# A500_GRAKA_26.net
KiCad netlist of a schematic drawn in EAGLE
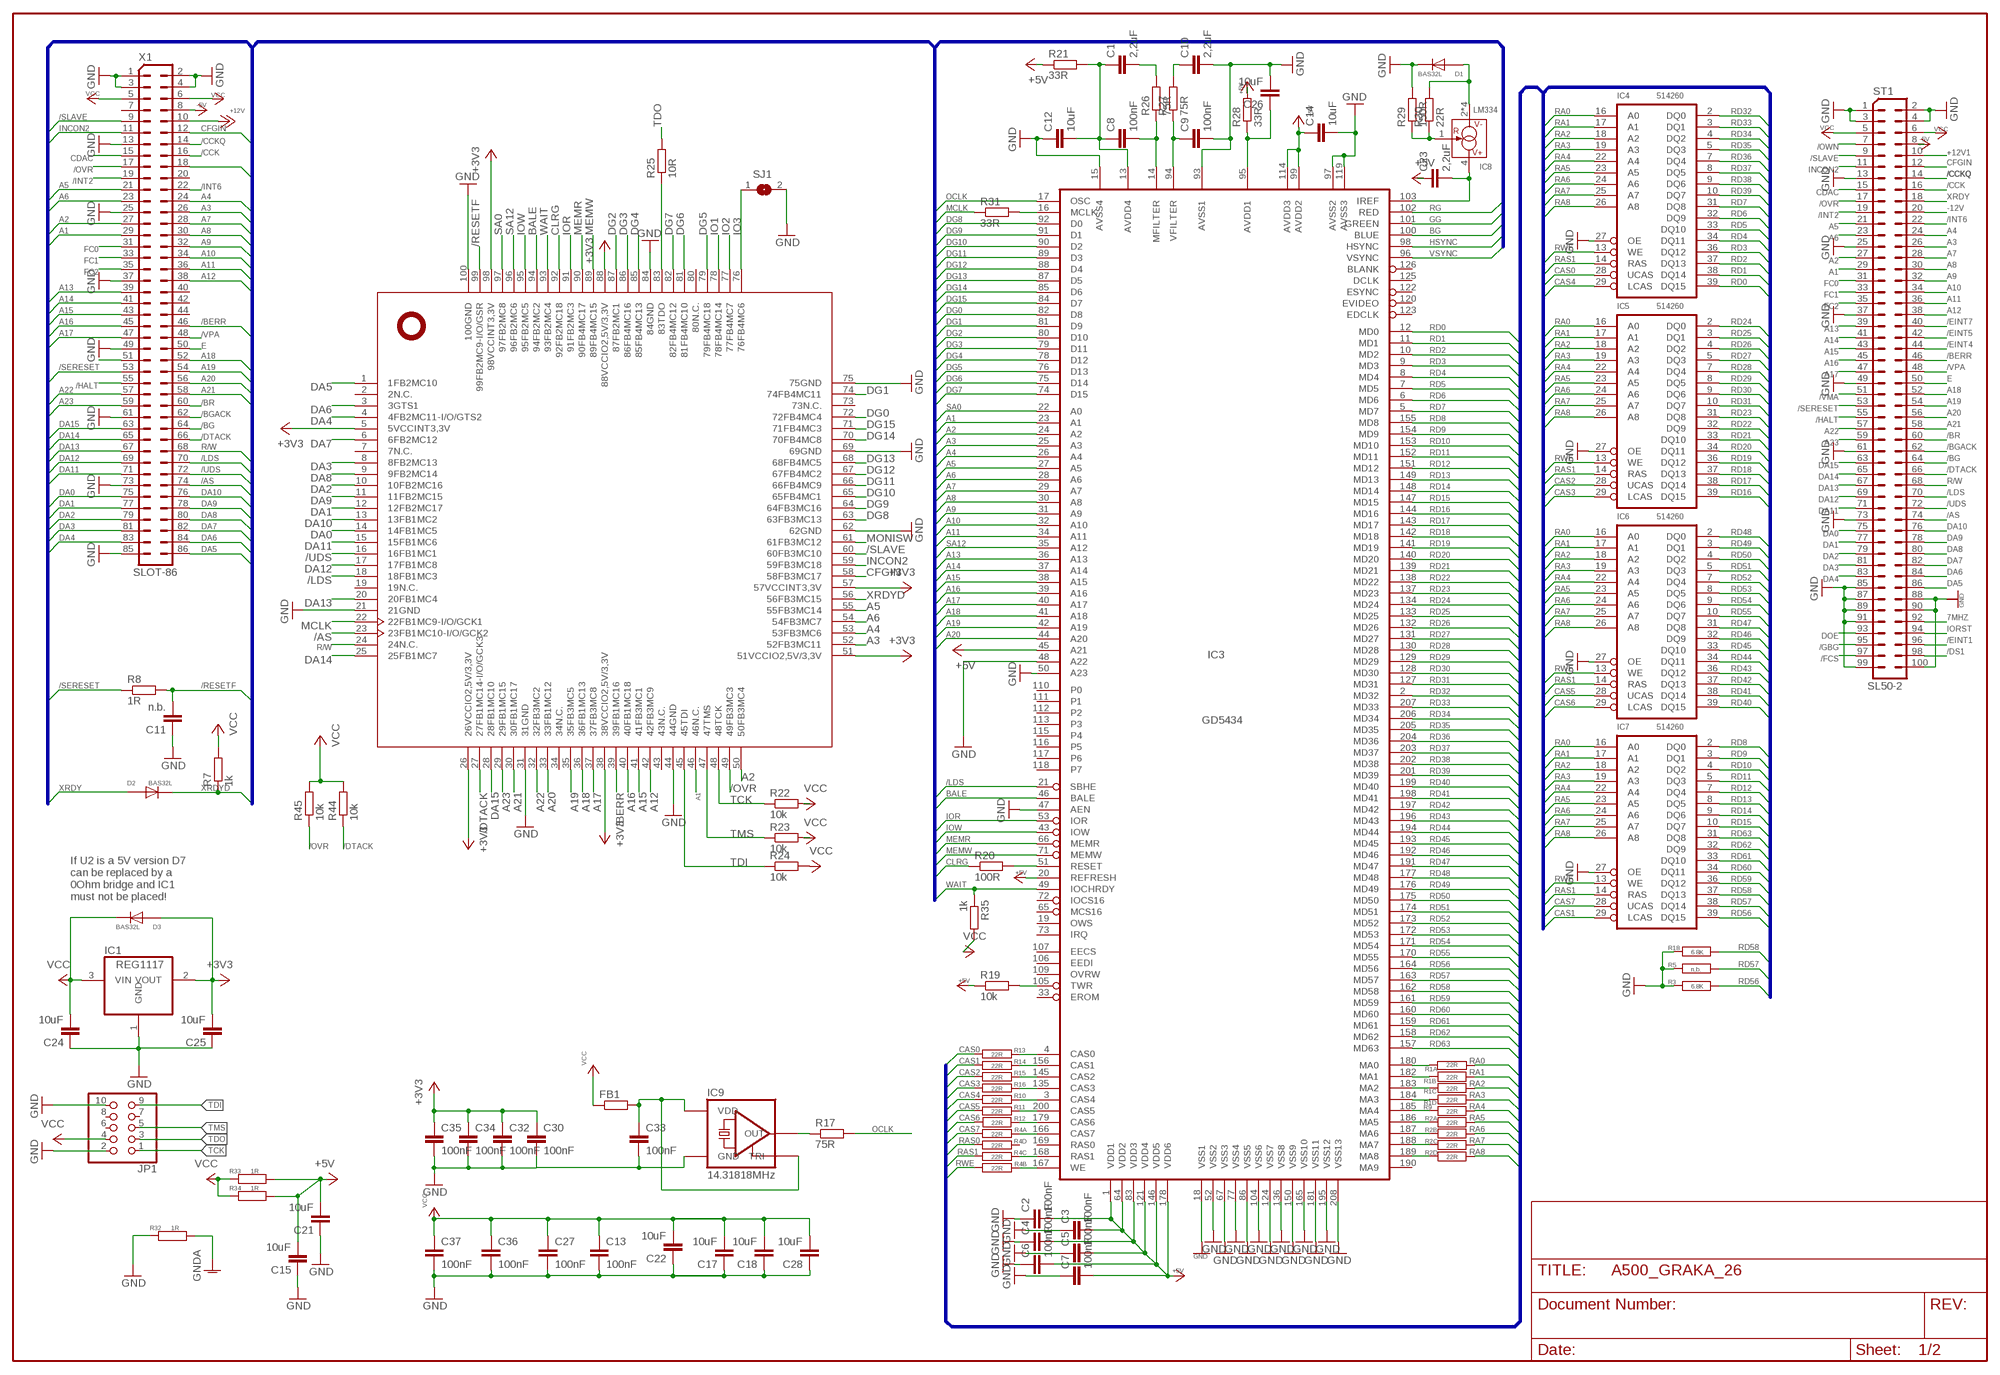
[diagram p0: schematic, sheet 1]
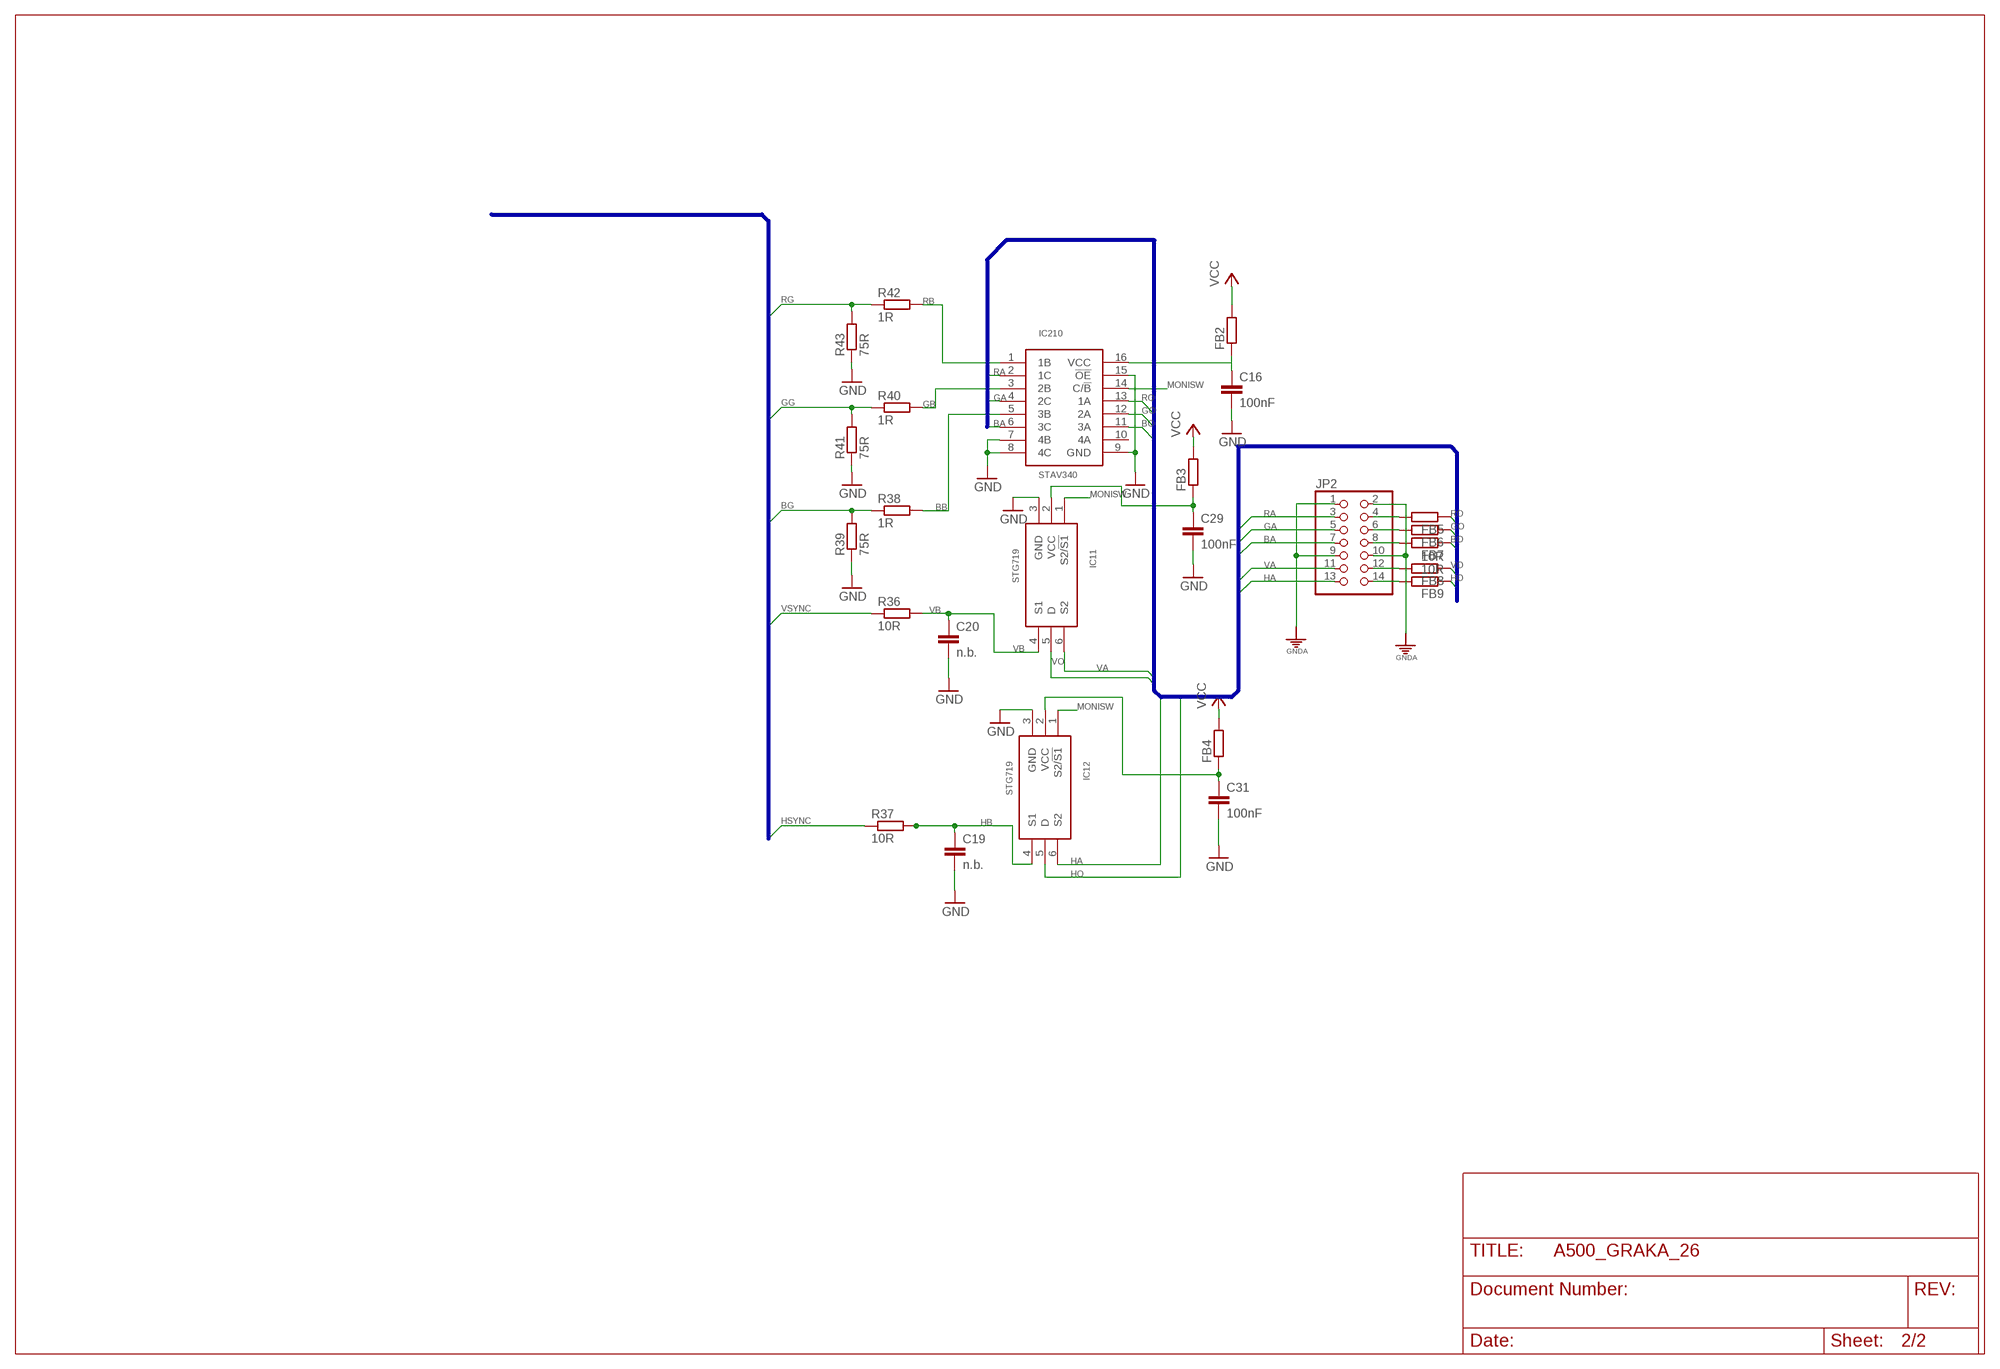
[diagram p1: schematic, sheet 2]

(export (version "E")
  (design (tool "Eeschema 10.0.6"))
  (components
    (comp (ref "C1")
      (value "2,2uF")
      (footprint "eagle-import:C0805K")
      (libsource (lib "eagle-import") (part "C-EUC0805K"))
    )
    (comp (ref "C2")
      (value "100nF")
      (footprint "eagle-import:C0805K")
      (libsource (lib "eagle-import") (part "C-EUC0805K"))
    )
    (comp (ref "C3")
      (value "100nF")
      (footprint "eagle-import:C0805K")
      (libsource (lib "eagle-import") (part "C-EUC0805K"))
    )
    (comp (ref "C4")
      (value "100nF")
      (footprint "eagle-import:C0805K")
      (libsource (lib "eagle-import") (part "C-EUC0805K"))
    )
    (comp (ref "C5")
      (value "100nF")
      (footprint "eagle-import:C0805K")
      (libsource (lib "eagle-import") (part "C-EUC0805K"))
    )
    (comp (ref "C6")
      (value "100nF")
      (footprint "eagle-import:C0805K")
      (libsource (lib "eagle-import") (part "C-EUC0805K"))
    )
    (comp (ref "C7")
      (value "100nF")
      (footprint "eagle-import:C0805K")
      (libsource (lib "eagle-import") (part "C-EUC0805K"))
    )
    (comp (ref "C8")
      (value "100nF")
      (footprint "eagle-import:C0805K")
      (libsource (lib "eagle-import") (part "C-EUC0805K"))
    )
    (comp (ref "C9")
      (value "100nF")
      (footprint "eagle-import:C0805K")
      (libsource (lib "eagle-import") (part "C-EUC0805K"))
    )
    (comp (ref "C10")
      (value "2,2uF")
      (footprint "eagle-import:C0805K")
      (libsource (lib "eagle-import") (part "C-EUC0805K"))
    )
    (comp (ref "C11")
      (value "n.b.")
      (footprint "eagle-import:C0805K")
      (libsource (lib "eagle-import") (part "C-EUC0805K"))
    )
    (comp (ref "C12")
      (value "10uF")
      (footprint "eagle-import:C0805K")
      (libsource (lib "eagle-import") (part "C-EUC0805K"))
    )
    (comp (ref "C13")
      (value "100nF")
      (footprint "eagle-import:C0805K")
      (libsource (lib "eagle-import") (part "C-EUC0805K"))
    )
    (comp (ref "C14")
      (value "10uF")
      (footprint "eagle-import:C0805K")
      (libsource (lib "eagle-import") (part "C-EUC0805K"))
    )
    (comp (ref "C15")
      (value "10uF")
      (footprint "eagle-import:C0805K")
      (libsource (lib "eagle-import") (part "C-EUC0805K"))
    )
    (comp (ref "C17")
      (value "10uF")
      (footprint "eagle-import:C0805K")
      (libsource (lib "eagle-import") (part "C-EUC0805K"))
    )
    (comp (ref "C18")
      (value "10uF")
      (footprint "eagle-import:C0805K")
      (libsource (lib "eagle-import") (part "C-EUC0805K"))
    )
    (comp (ref "C21")
      (value "10uF")
      (footprint "eagle-import:C0805K")
      (libsource (lib "eagle-import") (part "C-EUC0805K"))
    )
    (comp (ref "C22")
      (value "10uF")
      (footprint "eagle-import:C0805K")
      (libsource (lib "eagle-import") (part "C-EUC0805K"))
    )
    (comp (ref "C23")
      (value "2,2uF")
      (footprint "eagle-import:C0805K")
      (libsource (lib "eagle-import") (part "C-EUC0805K"))
    )
    (comp (ref "C24")
      (value "10uF")
      (footprint "eagle-import:C0805K")
      (libsource (lib "eagle-import") (part "C-EUC0805K"))
    )
    (comp (ref "C25")
      (value "10uF")
      (footprint "eagle-import:C0805K")
      (libsource (lib "eagle-import") (part "C-EUC0805K"))
    )
    (comp (ref "C26")
      (value "10uF")
      (footprint "eagle-import:C0805K")
      (libsource (lib "eagle-import") (part "C-EUC0805K"))
    )
    (comp (ref "C27")
      (value "100nF")
      (footprint "eagle-import:C0805K")
      (libsource (lib "eagle-import") (part "C-EUC0805K"))
    )
    (comp (ref "C28")
      (value "10uF")
      (footprint "eagle-import:C0805K")
      (libsource (lib "eagle-import") (part "C-EUC0805K"))
    )
    (comp (ref "C30")
      (value "100nF")
      (footprint "eagle-import:C0805K")
      (libsource (lib "eagle-import") (part "C-EUC0805K"))
    )
    (comp (ref "C32")
      (value "100nF")
      (footprint "eagle-import:C0805K")
      (libsource (lib "eagle-import") (part "C-EUC0805K"))
    )
    (comp (ref "C33")
      (value "100nF")
      (footprint "eagle-import:C0805K")
      (libsource (lib "eagle-import") (part "C-EUC0805K"))
    )
    (comp (ref "C34")
      (value "100nF")
      (footprint "eagle-import:C0805K")
      (libsource (lib "eagle-import") (part "C-EUC0805K"))
    )
    (comp (ref "C35")
      (value "100nF")
      (footprint "eagle-import:C0805K")
      (libsource (lib "eagle-import") (part "C-EUC0805K"))
    )
    (comp (ref "C36")
      (value "100nF")
      (footprint "eagle-import:C0805K")
      (libsource (lib "eagle-import") (part "C-EUC0805K"))
    )
    (comp (ref "C37")
      (value "100nF")
      (footprint "eagle-import:C0805K")
      (libsource (lib "eagle-import") (part "C-EUC0805K"))
    )
    (comp (ref "D1")
      (value "BAS32L")
      (footprint "eagle-import:SOD-80")
      (libsource (lib "eagle-import") (part "D-BAS32L"))
    )
    (comp (ref "D2")
      (value "BAS32L")
      (footprint "eagle-import:SOD-80")
      (libsource (lib "eagle-import") (part "D-BAS32L"))
    )
    (comp (ref "D3")
      (value "BAS32L")
      (footprint "eagle-import:SOD-80")
      (libsource (lib "eagle-import") (part "D-BAS32L"))
    )
    (comp (ref "FB1")
      (value "R-EU_R0805")
      (footprint "eagle-import:R0805")
      (libsource (lib "eagle-import") (part "R-EU_R0805"))
    )
    (comp (ref "IC1")
      (value "REG1117")
      (footprint "eagle-import:SOT223")
      (libsource (lib "eagle-import") (part "REG1117"))
    )
    (comp (ref "IC2")
      (value "XC95144XLTQ100")
      (footprint "eagle-import:TQ100")
      (libsource (lib "eagle-import") (part "XC9572XLTQ100"))
    )
    (comp (ref "IC3")
      (value "GD5434")
      (footprint "eagle-import:PQFP-208@3")
      (libsource (lib "eagle-import") (part "GD5434@3"))
    )
    (comp (ref "IC4")
      (value "514260")
      (footprint "eagle-import:SOJ40_4")
      (libsource (lib "eagle-import") (part "514260"))
    )
    (comp (ref "IC5")
      (value "514260")
      (footprint "eagle-import:SOJ40_4")
      (libsource (lib "eagle-import") (part "514260"))
    )
    (comp (ref "IC6")
      (value "514260")
      (footprint "eagle-import:SOJ40_4")
      (libsource (lib "eagle-import") (part "514260"))
    )
    (comp (ref "IC7")
      (value "514260")
      (footprint "eagle-import:SOJ40_4")
      (libsource (lib "eagle-import") (part "514260"))
    )
    (comp (ref "IC8")
      (value "LM334")
      (footprint "eagle-import:SO08")
      (libsource (lib "eagle-import") (part "LM34M(TI)3"))
    )
    (comp (ref "IC9")
      (value "14.31818MHz")
      (footprint "eagle-import:7X5")
      (libsource (lib "eagle-import") (part "CSX-750FCFC(5V)"))
    )
    (comp (ref "JP1")
      (value "PINHD-2X5_2.54-SMD")
      (footprint "eagle-import:2X05SMD")
      (libsource (lib "eagle-import") (part "PINHD-2X5_2.54-SMD"))
    )
    (comp (ref "R1")
      (value "22R")
      (footprint "eagle-import:R-NETZ")
      (libsource (lib "eagle-import") (part "R-NETZ"))
    )
    (comp (ref "R2")
      (value "22R")
      (footprint "eagle-import:R-NETZ")
      (libsource (lib "eagle-import") (part "R-NETZ"))
    )
    (comp (ref "R3")
      (value "6.8K")
      (footprint "eagle-import:0805@2")
      (libsource (lib "eagle-import") (part "R-MELF@4"))
    )
    (comp (ref "R4")
      (value "22R")
      (footprint "eagle-import:R-NETZ")
      (libsource (lib "eagle-import") (part "R-NETZ"))
    )
    (comp (ref "R5")
      (value "n.b.")
      (footprint "eagle-import:0805@2")
      (libsource (lib "eagle-import") (part "R-MELF@4"))
    )
    (comp (ref "R7")
      (value "1k")
      (footprint "eagle-import:R0805")
      (libsource (lib "eagle-import") (part "R-EU_R0805"))
    )
    (comp (ref "R8")
      (value "1R")
      (footprint "eagle-import:R0805")
      (libsource (lib "eagle-import") (part "R-EU_R0805"))
    )
    (comp (ref "R9")
      (value "22R")
      (footprint "eagle-import:0805@2")
      (libsource (lib "eagle-import") (part "R-MELF@4"))
    )
    (comp (ref "R10")
      (value "22R")
      (footprint "eagle-import:0805@2")
      (libsource (lib "eagle-import") (part "R-MELF@4"))
    )
    (comp (ref "R11")
      (value "22R")
      (footprint "eagle-import:0805@2")
      (libsource (lib "eagle-import") (part "R-MELF@4"))
    )
    (comp (ref "R12")
      (value "22R")
      (footprint "eagle-import:0805@2")
      (libsource (lib "eagle-import") (part "R-MELF@4"))
    )
    (comp (ref "R13")
      (value "22R")
      (footprint "eagle-import:0805@2")
      (libsource (lib "eagle-import") (part "R-MELF@4"))
    )
    (comp (ref "R14")
      (value "22R")
      (footprint "eagle-import:0805@2")
      (libsource (lib "eagle-import") (part "R-MELF@4"))
    )
    (comp (ref "R15")
      (value "22R")
      (footprint "eagle-import:0805@2")
      (libsource (lib "eagle-import") (part "R-MELF@4"))
    )
    (comp (ref "R16")
      (value "22R")
      (footprint "eagle-import:0805@2")
      (libsource (lib "eagle-import") (part "R-MELF@4"))
    )
    (comp (ref "R17")
      (value "75R")
      (footprint "eagle-import:R0805")
      (libsource (lib "eagle-import") (part "R-EU_R0805"))
    )
    (comp (ref "R18")
      (value "6.8K")
      (footprint "eagle-import:0805@2")
      (libsource (lib "eagle-import") (part "R-MELF@4"))
    )
    (comp (ref "R19")
      (value "10k")
      (footprint "eagle-import:R0805")
      (libsource (lib "eagle-import") (part "R-EU_R0805"))
    )
    (comp (ref "R20")
      (value "100R")
      (footprint "eagle-import:R0805")
      (libsource (lib "eagle-import") (part "R-EU_R0805"))
    )
    (comp (ref "R21")
      (value "33R")
      (footprint "eagle-import:R0805")
      (libsource (lib "eagle-import") (part "R-EU_R0805"))
    )
    (comp (ref "R22")
      (value "10k")
      (footprint "eagle-import:R0805")
      (libsource (lib "eagle-import") (part "R-EU_R0805"))
    )
    (comp (ref "R23")
      (value "10k")
      (footprint "eagle-import:R0805")
      (libsource (lib "eagle-import") (part "R-EU_R0805"))
    )
    (comp (ref "R24")
      (value "10k")
      (footprint "eagle-import:R0805")
      (libsource (lib "eagle-import") (part "R-EU_R0805"))
    )
    (comp (ref "R25")
      (value "10R")
      (footprint "eagle-import:R0805")
      (libsource (lib "eagle-import") (part "R-EU_R0805"))
    )
    (comp (ref "R26")
      (value "75R")
      (footprint "eagle-import:R0805")
      (libsource (lib "eagle-import") (part "R-EU_R0805"))
    )
    (comp (ref "R27")
      (value "75R")
      (footprint "eagle-import:R0805")
      (libsource (lib "eagle-import") (part "R-EU_R0805"))
    )
    (comp (ref "R28")
      (value "33R")
      (footprint "eagle-import:R0805")
      (libsource (lib "eagle-import") (part "R-EU_R0805"))
    )
    (comp (ref "R29")
      (value "150R")
      (footprint "eagle-import:R0805")
      (libsource (lib "eagle-import") (part "R-EU_R0805"))
    )
    (comp (ref "R30")
      (value "22R")
      (footprint "eagle-import:R0805")
      (libsource (lib "eagle-import") (part "R-EU_R0805"))
    )
    (comp (ref "R31")
      (value "33R")
      (footprint "eagle-import:R0805")
      (libsource (lib "eagle-import") (part "R-EU_R0805"))
    )
    (comp (ref "R32")
      (value "1R")
      (footprint "eagle-import:0204")
      (libsource (lib "eagle-import") (part "R-MELF@3"))
    )
    (comp (ref "R33")
      (value "1R")
      (footprint "eagle-import:0204")
      (libsource (lib "eagle-import") (part "R-MELF@3"))
    )
    (comp (ref "R34")
      (value "1R")
      (footprint "eagle-import:0204")
      (libsource (lib "eagle-import") (part "R-MELF@3"))
    )
    (comp (ref "R35")
      (value "1k")
      (footprint "eagle-import:R0805")
      (libsource (lib "eagle-import") (part "R-EU_R0805"))
    )
    (comp (ref "R44")
      (value "10k")
      (footprint "eagle-import:R0805")
      (libsource (lib "eagle-import") (part "R-EU_R0805"))
    )
    (comp (ref "R45")
      (value "10k")
      (footprint "eagle-import:R0805")
      (libsource (lib "eagle-import") (part "R-EU_R0805"))
    )
    (comp (ref "SJ1") (value "SJ") (footprint "eagle-import:SJ") (libsource (lib "eagle-import") (part "SJ")))
    (comp (ref "ST1")
      (value "SL50-2")
      (footprint "eagle-import:LKOT-501")
      (libsource (lib "eagle-import") (part "SL50-2@3"))
    )
    (comp (ref "X1")
      (value "SLOT-86")
      (footprint "eagle-import:SLOT-86")
      (libsource (lib "eagle-import") (part "SLOT-86"))
    )
    (comp (ref "C16")
      (value "100nF")
      (footprint "eagle-import:C0805K")
      (libsource (lib "eagle-import") (part "C-EUC0805K"))
    )
    (comp (ref "C19")
      (value "n.b.")
      (footprint "eagle-import:C0805K")
      (libsource (lib "eagle-import") (part "C-EUC0805K"))
    )
    (comp (ref "C20")
      (value "n.b.")
      (footprint "eagle-import:C0805K")
      (libsource (lib "eagle-import") (part "C-EUC0805K"))
    )
    (comp (ref "C29")
      (value "100nF")
      (footprint "eagle-import:C0805K")
      (libsource (lib "eagle-import") (part "C-EUC0805K"))
    )
    (comp (ref "C31")
      (value "100nF")
      (footprint "eagle-import:C0805K")
      (libsource (lib "eagle-import") (part "C-EUC0805K"))
    )
    (comp (ref "FB2")
      (value "R-EU_R0805")
      (footprint "eagle-import:R0805")
      (libsource (lib "eagle-import") (part "R-EU_R0805"))
    )
    (comp (ref "FB3")
      (value "R-EU_R0805")
      (footprint "eagle-import:R0805")
      (libsource (lib "eagle-import") (part "R-EU_R0805"))
    )
    (comp (ref "FB4")
      (value "R-EU_R0805")
      (footprint "eagle-import:R0805")
      (libsource (lib "eagle-import") (part "R-EU_R0805"))
    )
    (comp (ref "FB5")
      (value "R-EU_R0805")
      (footprint "eagle-import:R0805")
      (libsource (lib "eagle-import") (part "R-EU_R0805"))
    )
    (comp (ref "FB6")
      (value "R-EU_R0805")
      (footprint "eagle-import:R0805")
      (libsource (lib "eagle-import") (part "R-EU_R0805"))
    )
    (comp (ref "FB7")
      (value "R-EU_R0805")
      (footprint "eagle-import:R0805")
      (libsource (lib "eagle-import") (part "R-EU_R0805"))
    )
    (comp (ref "FB8")
      (value "10R")
      (footprint "eagle-import:R0805")
      (libsource (lib "eagle-import") (part "R-EU_R0805"))
    )
    (comp (ref "FB9")
      (value "10R")
      (footprint "eagle-import:R0805")
      (libsource (lib "eagle-import") (part "R-EU_R0805"))
    )
    (comp (ref "IC11")
      (value "STG719")
      (footprint "eagle-import:SOT23-6L")
      (libsource (lib "eagle-import") (part "STG719"))
    )
    (comp (ref "IC12")
      (value "STG719")
      (footprint "eagle-import:SOT23-6L")
      (libsource (lib "eagle-import") (part "STG719"))
    )
    (comp (ref "IC210")
      (value "STAV340")
      (footprint "eagle-import:TSSOP16")
      (libsource (lib "eagle-import") (part "STAV340"))
    )
    (comp (ref "JP2")
      (value "PINHD-2X7_2.54-SMD")
      (footprint "eagle-import:2X07SMD")
      (libsource (lib "eagle-import") (part "PINHD-2X7_2.54-SMD"))
    )
    (comp (ref "R36")
      (value "10R")
      (footprint "eagle-import:R0805")
      (libsource (lib "eagle-import") (part "R-EU_R0805"))
    )
    (comp (ref "R37")
      (value "10R")
      (footprint "eagle-import:R0805")
      (libsource (lib "eagle-import") (part "R-EU_R0805"))
    )
    (comp (ref "R38")
      (value "1R")
      (footprint "eagle-import:R0805")
      (libsource (lib "eagle-import") (part "R-EU_R0805"))
    )
    (comp (ref "R39")
      (value "75R")
      (footprint "eagle-import:R0805")
      (libsource (lib "eagle-import") (part "R-EU_R0805"))
    )
    (comp (ref "R40")
      (value "1R")
      (footprint "eagle-import:R0805")
      (libsource (lib "eagle-import") (part "R-EU_R0805"))
    )
    (comp (ref "R41")
      (value "75R")
      (footprint "eagle-import:R0805")
      (libsource (lib "eagle-import") (part "R-EU_R0805"))
    )
    (comp (ref "R42")
      (value "1R")
      (footprint "eagle-import:R0805")
      (libsource (lib "eagle-import") (part "R-EU_R0805"))
    )
    (comp (ref "R43")
      (value "75R")
      (footprint "eagle-import:R0805")
      (libsource (lib "eagle-import") (part "R-EU_R0805"))
    )
  )
  (nets
    (net (code "1") (name "+3V3") (class "Default")
      (node (ref "C25") (pin "2") (pinfunction "2_2") (pintype "passive"))
      (node (ref "C30") (pin "1") (pinfunction "1_1") (pintype "passive"))
      (node (ref "C32") (pin "1") (pinfunction "1_1") (pintype "passive"))
      (node (ref "C34") (pin "1") (pinfunction "1_1") (pintype "passive"))
      (node (ref "C35") (pin "1") (pinfunction "1_1") (pintype "passive"))
      (node (ref "D3") (pin "1") (pinfunction "A_1") (pintype "bidirectional"))
      (node (ref "IC1") (pin "2") (pinfunction "VOUT_2") (pintype "output"))
      (node (ref "IC2") (pin "26") (pinfunction "26VCCIO2,5V/3,3V_26") (pintype "bidirectional"))
      (node (ref "IC2") (pin "38") (pinfunction "38VCCIO2,5V/3,3V_38") (pintype "bidirectional"))
      (node (ref "IC2") (pin "5") (pinfunction "5VCCINT3,3V_5") (pintype "bidirectional"))
      (node (ref "IC2") (pin "51") (pinfunction "51VCCIO2,5V/3,3V_51") (pintype "bidirectional"))
      (node (ref "IC2") (pin "57") (pinfunction "57VCCINT3,3V_57") (pintype "bidirectional"))
      (node (ref "IC2") (pin "88") (pinfunction "88VCCIO2,5V/3,3V_88") (pintype "bidirectional"))
      (node (ref "IC2") (pin "98") (pinfunction "98VCCINT3,3V_98") (pintype "bidirectional"))
    )
    (net (code "2") (name "+5V") (class "Default")
      (node (ref "C14") (pin "1") (pinfunction "1_1") (pintype "passive"))
      (node (ref "C15") (pin "2") (pinfunction "2_2") (pintype "passive"))
      (node (ref "C2") (pin "2") (pinfunction "2_2") (pintype "passive"))
      (node (ref "C21") (pin "2") (pinfunction "2_2") (pintype "passive"))
      (node (ref "C23") (pin "1") (pinfunction "1_1") (pintype "passive"))
      (node (ref "C3") (pin "2") (pinfunction "2_2") (pintype "passive"))
      (node (ref "C4") (pin "2") (pinfunction "2_2") (pintype "passive"))
      (node (ref "C5") (pin "2") (pinfunction "2_2") (pintype "passive"))
      (node (ref "C6") (pin "2") (pinfunction "2_2") (pintype "passive"))
      (node (ref "C7") (pin "2") (pinfunction "2_2") (pintype "passive"))
      (node (ref "IC3") (pin "1") (pinfunction "VDD1_1") (pintype "power_in"))
      (node (ref "IC3") (pin "114") (pinfunction "AVDD3_114") (pintype "power_in"))
      (node (ref "IC3") (pin "121") (pinfunction "VDD4_121") (pintype "power_in"))
      (node (ref "IC3") (pin "146") (pinfunction "VDD5_146") (pintype "power_in"))
      (node (ref "IC3") (pin "178") (pinfunction "VDD6_178") (pintype "power_in"))
      (node (ref "IC3") (pin "20") (pinfunction "REFRESH_20") (pintype "input"))
      (node (ref "IC3") (pin "45") (pinfunction "A21_45") (pintype "input"))
      (node (ref "IC3") (pin "64") (pinfunction "VDD2_64") (pintype "power_in"))
      (node (ref "IC3") (pin "83") (pinfunction "VDD3_83") (pintype "power_in"))
      (node (ref "IC3") (pin "99") (pinfunction "AVDD2_99") (pintype "power_in"))
      (node (ref "R19") (pin "1") (pinfunction "1_1") (pintype "passive"))
      (node (ref "R21") (pin "1") (pinfunction "1_1") (pintype "passive"))
      (node (ref "R28") (pin "2") (pinfunction "2_2") (pintype "passive"))
      (node (ref "R33") (pin "1") (pinfunction "P$1_1") (pintype "bidirectional"))
      (node (ref "R34") (pin "1") (pinfunction "P$1_1") (pintype "bidirectional"))
    )
    (net (code "3") (name "+12V") (class "Default")
      (node (ref "X1") (pin "10") (pinfunction "10_10") (pintype "passive"))
    )
    (net (code "4") (name "+12V1") (class "Default")
      (node (ref "ST1") (pin "10") (pinfunction "10_10") (pintype "passive"))
    )
    (net (code "5") (name "-5V") (class "Default")
      (node (ref "ST1") (pin "8") (pinfunction "8_8") (pintype "passive"))
      (node (ref "X1") (pin "8") (pinfunction "8_8") (pintype "passive"))
    )
    (net (code "7") (name "7MHZ") (class "Default")
      (node (ref "ST1") (pin "92") (pinfunction "92_92") (pintype "passive"))
    )
    (net (code "8") (name "A1") (class "Default")
      (node (ref "IC2") (pin "46") (pinfunction "46N.C._46") (pintype "bidirectional"))
      (node (ref "IC3") (pin "23") (pinfunction "A1_23") (pintype "input"))
      (node (ref "ST1") (pin "29") (pinfunction "29_29") (pintype "passive"))
      (node (ref "X1") (pin "29") (pinfunction "29_29") (pintype "passive"))
    )
    (net (code "9") (name "A2") (class "Default")
      (node (ref "IC2") (pin "50") (pinfunction "50FB3MC4_50") (pintype "bidirectional"))
      (node (ref "IC3") (pin "24") (pinfunction "A2_24") (pintype "input"))
      (node (ref "ST1") (pin "27") (pinfunction "27_27") (pintype "passive"))
      (node (ref "X1") (pin "27") (pinfunction "27_27") (pintype "passive"))
    )
    (net (code "10") (name "A3") (class "Default")
      (node (ref "IC2") (pin "52") (pinfunction "52FB3MC11_52") (pintype "bidirectional"))
      (node (ref "IC3") (pin "25") (pinfunction "A3_25") (pintype "input"))
      (node (ref "ST1") (pin "26") (pinfunction "26_26") (pintype "passive"))
      (node (ref "X1") (pin "26") (pinfunction "26_26") (pintype "passive"))
    )
    (net (code "11") (name "A4") (class "Default")
      (node (ref "IC2") (pin "53") (pinfunction "53FB3MC6_53") (pintype "bidirectional"))
      (node (ref "IC3") (pin "26") (pinfunction "A4_26") (pintype "input"))
      (node (ref "ST1") (pin "24") (pinfunction "24_24") (pintype "passive"))
      (node (ref "X1") (pin "24") (pinfunction "24_24") (pintype "passive"))
    )
    (net (code "12") (name "A5") (class "Default")
      (node (ref "IC2") (pin "55") (pinfunction "55FB3MC14_55") (pintype "bidirectional"))
      (node (ref "IC3") (pin "27") (pinfunction "A5_27") (pintype "input"))
      (node (ref "ST1") (pin "21") (pinfunction "21_21") (pintype "passive"))
      (node (ref "X1") (pin "21") (pinfunction "21_21") (pintype "passive"))
    )
    (net (code "13") (name "A6") (class "Default")
      (node (ref "IC2") (pin "54") (pinfunction "54FB3MC7_54") (pintype "bidirectional"))
      (node (ref "IC3") (pin "28") (pinfunction "A6_28") (pintype "input"))
      (node (ref "ST1") (pin "23") (pinfunction "23_23") (pintype "passive"))
      (node (ref "X1") (pin "23") (pinfunction "23_23") (pintype "passive"))
    )
    (net (code "14") (name "A7") (class "Default")
      (node (ref "IC3") (pin "29") (pinfunction "A7_29") (pintype "input"))
      (node (ref "ST1") (pin "28") (pinfunction "28_28") (pintype "passive"))
      (node (ref "X1") (pin "28") (pinfunction "28_28") (pintype "passive"))
    )
    (net (code "15") (name "A8") (class "Default")
      (node (ref "IC3") (pin "30") (pinfunction "A8_30") (pintype "input"))
      (node (ref "ST1") (pin "30") (pinfunction "30_30") (pintype "passive"))
      (node (ref "X1") (pin "30") (pinfunction "30_30") (pintype "passive"))
    )
    (net (code "16") (name "A9") (class "Default")
      (node (ref "IC3") (pin "31") (pinfunction "A9_31") (pintype "input"))
      (node (ref "ST1") (pin "32") (pinfunction "32_32") (pintype "passive"))
      (node (ref "X1") (pin "32") (pinfunction "32_32") (pintype "passive"))
    )
    (net (code "17") (name "A10") (class "Default")
      (node (ref "IC3") (pin "32") (pinfunction "A10_32") (pintype "input"))
      (node (ref "ST1") (pin "34") (pinfunction "34_34") (pintype "passive"))
      (node (ref "X1") (pin "34") (pinfunction "34_34") (pintype "passive"))
    )
    (net (code "18") (name "A11") (class "Default")
      (node (ref "IC3") (pin "34") (pinfunction "A11_34") (pintype "input"))
      (node (ref "ST1") (pin "36") (pinfunction "36_36") (pintype "passive"))
      (node (ref "X1") (pin "36") (pinfunction "36_36") (pintype "passive"))
    )
    (net (code "19") (name "A12") (class "Default")
      (node (ref "IC2") (pin "42") (pinfunction "42FB3MC9_42") (pintype "bidirectional"))
      (node (ref "ST1") (pin "38") (pinfunction "38_38") (pintype "passive"))
      (node (ref "X1") (pin "38") (pinfunction "38_38") (pintype "passive"))
    )
    (net (code "20") (name "A13") (class "Default")
      (node (ref "IC3") (pin "36") (pinfunction "A13_36") (pintype "input"))
      (node (ref "ST1") (pin "39") (pinfunction "39_39") (pintype "passive"))
      (node (ref "X1") (pin "39") (pinfunction "39_39") (pintype "passive"))
    )
    (net (code "21") (name "A14") (class "Default")
      (node (ref "IC3") (pin "37") (pinfunction "A14_37") (pintype "input"))
      (node (ref "ST1") (pin "41") (pinfunction "41_41") (pintype "passive"))
      (node (ref "X1") (pin "41") (pinfunction "41_41") (pintype "passive"))
    )
    (net (code "22") (name "A15") (class "Default")
      (node (ref "IC2") (pin "41") (pinfunction "41FB3MC1_41") (pintype "bidirectional"))
      (node (ref "IC3") (pin "38") (pinfunction "A15_38") (pintype "input"))
      (node (ref "ST1") (pin "43") (pinfunction "43_43") (pintype "passive"))
      (node (ref "X1") (pin "43") (pinfunction "43_43") (pintype "passive"))
    )
    (net (code "23") (name "A16") (class "Default")
      (node (ref "IC2") (pin "40") (pinfunction "40FB1MC18_40") (pintype "bidirectional"))
      (node (ref "IC3") (pin "39") (pinfunction "A16_39") (pintype "input"))
      (node (ref "ST1") (pin "45") (pinfunction "45_45") (pintype "passive"))
      (node (ref "X1") (pin "45") (pinfunction "45_45") (pintype "passive"))
    )
    (net (code "24") (name "A17") (class "Default")
      (node (ref "IC2") (pin "37") (pinfunction "37FB3MC8_37") (pintype "bidirectional"))
      (node (ref "IC3") (pin "40") (pinfunction "A17_40") (pintype "input"))
      (node (ref "ST1") (pin "47") (pinfunction "47_47") (pintype "passive"))
      (node (ref "X1") (pin "47") (pinfunction "47_47") (pintype "passive"))
    )
    (net (code "25") (name "A18") (class "Default")
      (node (ref "IC2") (pin "36") (pinfunction "36FB1MC13_36") (pintype "bidirectional"))
      (node (ref "IC3") (pin "41") (pinfunction "A18_41") (pintype "input"))
      (node (ref "ST1") (pin "52") (pinfunction "52_52") (pintype "passive"))
      (node (ref "X1") (pin "52") (pinfunction "52_52") (pintype "passive"))
    )
    (net (code "26") (name "A19") (class "Default")
      (node (ref "IC2") (pin "35") (pinfunction "35FB3MC5_35") (pintype "bidirectional"))
      (node (ref "IC3") (pin "42") (pinfunction "A19_42") (pintype "input"))
      (node (ref "ST1") (pin "54") (pinfunction "54_54") (pintype "passive"))
      (node (ref "X1") (pin "54") (pinfunction "54_54") (pintype "passive"))
    )
    (net (code "27") (name "A20") (class "Default")
      (node (ref "IC2") (pin "33") (pinfunction "33FB1MC12_33") (pintype "bidirectional"))
      (node (ref "IC3") (pin "44") (pinfunction "A20_44") (pintype "input"))
      (node (ref "ST1") (pin "56") (pinfunction "56_56") (pintype "passive"))
      (node (ref "X1") (pin "56") (pinfunction "56_56") (pintype "passive"))
    )
    (net (code "28") (name "A21") (class "Default")
      (node (ref "IC2") (pin "30") (pinfunction "30FB1MC17_30") (pintype "bidirectional"))
      (node (ref "ST1") (pin "58") (pinfunction "58_58") (pintype "passive"))
      (node (ref "X1") (pin "58") (pinfunction "58_58") (pintype "passive"))
    )
    (net (code "29") (name "A22") (class "Default")
      (node (ref "IC2") (pin "32") (pinfunction "32FB3MC2_32") (pintype "bidirectional"))
      (node (ref "ST1") (pin "57") (pinfunction "57_57") (pintype "passive"))
      (node (ref "X1") (pin "57") (pinfunction "57_57") (pintype "passive"))
    )
    (net (code "30") (name "A23") (class "Default")
      (node (ref "IC2") (pin "29") (pinfunction "29FB1MC15_29") (pintype "bidirectional"))
      (node (ref "ST1") (pin "59") (pinfunction "59_59") (pintype "passive"))
      (node (ref "X1") (pin "59") (pinfunction "59_59") (pintype "passive"))
    )
    (net (code "31") (name "BA") (class "Default")
      (node (ref "IC210") (pin "6") (pinfunction "3C_6") (pintype "bidirectional"))
      (node (ref "JP2") (pin "7") (pinfunction "7_7") (pintype "passive"))
    )
    (net (code "32") (name "BALE") (class "Default")
      (node (ref "IC2") (pin "94") (pinfunction "94FB2MC2_94") (pintype "bidirectional"))
      (node (ref "IC3") (pin "46") (pinfunction "BALE_46") (pintype "input"))
    )
    (net (code "33") (name "BB") (class "Default")
      (node (ref "IC210") (pin "5") (pinfunction "3B_5") (pintype "bidirectional"))
      (node (ref "R38") (pin "2") (pinfunction "2_2") (pintype "passive"))
    )
    (net (code "34") (name "BG") (class "Default")
      (node (ref "IC3") (pin "100") (pinfunction "BLUE_100") (pintype "output"))
      (node (ref "R38") (pin "1") (pinfunction "1_1") (pintype "passive"))
      (node (ref "R39") (pin "2") (pinfunction "2_2") (pintype "passive"))
    )
    (net (code "35") (name "BO") (class "Default")
      (node (ref "FB7") (pin "1") (pinfunction "1_1") (pintype "passive"))
      (node (ref "IC210") (pin "11") (pinfunction "3A_11") (pintype "bidirectional"))
    )
    (net (code "36") (name "CAS0") (class "Default")
      (node (ref "IC4") (pin "28") (pinfunction "UCAS_28") (pintype "input"))
      (node (ref "R13") (pin "1") (pinfunction "P$1_1") (pintype "bidirectional"))
    )
    (net (code "37") (name "CAS1") (class "Default")
      (node (ref "IC7") (pin "29") (pinfunction "LCAS_29") (pintype "input"))
      (node (ref "R14") (pin "1") (pinfunction "P$1_1") (pintype "bidirectional"))
    )
    (net (code "38") (name "CAS2") (class "Default")
      (node (ref "IC5") (pin "28") (pinfunction "UCAS_28") (pintype "input"))
      (node (ref "R15") (pin "1") (pinfunction "P$1_1") (pintype "bidirectional"))
    )
    (net (code "39") (name "CAS3") (class "Default")
      (node (ref "IC5") (pin "29") (pinfunction "LCAS_29") (pintype "input"))
      (node (ref "R16") (pin "1") (pinfunction "P$1_1") (pintype "bidirectional"))
    )
    (net (code "40") (name "CAS4") (class "Default")
      (node (ref "IC4") (pin "29") (pinfunction "LCAS_29") (pintype "input"))
      (node (ref "R10") (pin "1") (pinfunction "P$1_1") (pintype "bidirectional"))
    )
    (net (code "41") (name "CAS5") (class "Default")
      (node (ref "IC6") (pin "28") (pinfunction "UCAS_28") (pintype "input"))
      (node (ref "R11") (pin "1") (pinfunction "P$1_1") (pintype "bidirectional"))
    )
    (net (code "42") (name "CAS6") (class "Default")
      (node (ref "IC6") (pin "29") (pinfunction "LCAS_29") (pintype "input"))
      (node (ref "R12") (pin "2") (pinfunction "P$2_2") (pintype "bidirectional"))
    )
    (net (code "43") (name "CAS7") (class "Default")
      (node (ref "IC7") (pin "28") (pinfunction "UCAS_28") (pintype "input"))
      (node (ref "R4") (pin "P$1") (pinfunction "P$1_P$1") (pintype "bidirectional"))
    )
    (net (code "44") (name "CDAC") (class "Default")
      (node (ref "ST1") (pin "15") (pinfunction "15_15") (pintype "passive"))
      (node (ref "X1") (pin "15") (pinfunction "15_15") (pintype "passive"))
    )
    (net (code "45") (name "CFGIN") (class "Default")
      (node (ref "IC2") (pin "58") (pinfunction "58FB3MC17_58") (pintype "bidirectional"))
      (node (ref "ST1") (pin "12") (pinfunction "12_12") (pintype "passive"))
      (node (ref "X1") (pin "12") (pinfunction "12_12") (pintype "passive"))
    )
    (net (code "46") (name "CLRG") (class "Default")
      (node (ref "IC2") (pin "92") (pinfunction "92FB2MC18_92") (pintype "bidirectional"))
      (node (ref "R20") (pin "1") (pinfunction "1_1") (pintype "passive"))
    )
    (net (code "47") (name "DA0") (class "Default")
      (node (ref "IC2") (pin "14") (pinfunction "14FB1MC5_14") (pintype "bidirectional"))
      (node (ref "ST1") (pin "75") (pinfunction "75_75") (pintype "passive"))
      (node (ref "X1") (pin "75") (pinfunction "75_75") (pintype "passive"))
    )
    (net (code "48") (name "DA1") (class "Default")
      (node (ref "IC2") (pin "12") (pinfunction "12FB2MC17_12") (pintype "bidirectional"))
      (node (ref "ST1") (pin "77") (pinfunction "77_77") (pintype "passive"))
      (node (ref "X1") (pin "77") (pinfunction "77_77") (pintype "passive"))
    )
    (net (code "49") (name "DA2") (class "Default")
      (node (ref "IC2") (pin "10") (pinfunction "10FB2MC16_10") (pintype "bidirectional"))
      (node (ref "ST1") (pin "79") (pinfunction "79_79") (pintype "passive"))
      (node (ref "X1") (pin "79") (pinfunction "79_79") (pintype "passive"))
    )
    (net (code "50") (name "DA3") (class "Default")
      (node (ref "IC2") (pin "8") (pinfunction "8FB2MC13_8") (pintype "bidirectional"))
      (node (ref "ST1") (pin "81") (pinfunction "81_81") (pintype "passive"))
      (node (ref "X1") (pin "81") (pinfunction "81_81") (pintype "passive"))
    )
    (net (code "51") (name "DA4") (class "Default")
      (node (ref "IC2") (pin "4") (pinfunction "4FB2MC11-I/O/GTS2_4") (pintype "bidirectional"))
      (node (ref "ST1") (pin "83") (pinfunction "83_83") (pintype "passive"))
      (node (ref "X1") (pin "83") (pinfunction "83_83") (pintype "passive"))
    )
    (net (code "52") (name "DA5") (class "Default")
      (node (ref "IC2") (pin "1") (pinfunction "1FB2MC10_1") (pintype "bidirectional"))
      (node (ref "ST1") (pin "86") (pinfunction "86_86") (pintype "passive"))
      (node (ref "X1") (pin "86") (pinfunction "86_86") (pintype "passive"))
    )
    (net (code "53") (name "DA6") (class "Default")
      (node (ref "IC2") (pin "3") (pinfunction "3GTS1_3") (pintype "bidirectional"))
      (node (ref "ST1") (pin "84") (pinfunction "84_84") (pintype "passive"))
      (node (ref "X1") (pin "84") (pinfunction "84_84") (pintype "passive"))
    )
    (net (code "54") (name "DA7") (class "Default")
      (node (ref "IC2") (pin "6") (pinfunction "6FB2MC12_6") (pintype "bidirectional"))
      (node (ref "ST1") (pin "82") (pinfunction "82_82") (pintype "passive"))
      (node (ref "X1") (pin "82") (pinfunction "82_82") (pintype "passive"))
    )
    (net (code "55") (name "DA8") (class "Default")
      (node (ref "IC2") (pin "9") (pinfunction "9FB2MC14_9") (pintype "bidirectional"))
      (node (ref "ST1") (pin "80") (pinfunction "80_80") (pintype "passive"))
      (node (ref "X1") (pin "80") (pinfunction "80_80") (pintype "passive"))
    )
    (net (code "56") (name "DA9") (class "Default")
      (node (ref "IC2") (pin "11") (pinfunction "11FB2MC15_11") (pintype "bidirectional"))
      (node (ref "ST1") (pin "78") (pinfunction "78_78") (pintype "passive"))
      (node (ref "X1") (pin "78") (pinfunction "78_78") (pintype "passive"))
    )
    (net (code "57") (name "DA10") (class "Default")
      (node (ref "IC2") (pin "13") (pinfunction "13FB1MC2_13") (pintype "bidirectional"))
      (node (ref "ST1") (pin "76") (pinfunction "76_76") (pintype "passive"))
      (node (ref "X1") (pin "76") (pinfunction "76_76") (pintype "passive"))
    )
    (net (code "58") (name "DA11") (class "Default")
      (node (ref "IC2") (pin "15") (pinfunction "15FB1MC6_15") (pintype "bidirectional"))
      (node (ref "ST1") (pin "71") (pinfunction "71_71") (pintype "passive"))
      (node (ref "X1") (pin "71") (pinfunction "71_71") (pintype "passive"))
    )
    (net (code "59") (name "DA12") (class "Default")
      (node (ref "IC2") (pin "17") (pinfunction "17FB1MC8_17") (pintype "bidirectional"))
      (node (ref "ST1") (pin "69") (pinfunction "69_69") (pintype "passive"))
      (node (ref "X1") (pin "69") (pinfunction "69_69") (pintype "passive"))
    )
    (net (code "60") (name "DA13") (class "Default")
      (node (ref "IC2") (pin "20") (pinfunction "20FB1MC4_20") (pintype "bidirectional"))
      (node (ref "ST1") (pin "67") (pinfunction "67_67") (pintype "passive"))
      (node (ref "X1") (pin "67") (pinfunction "67_67") (pintype "passive"))
    )
    (net (code "61") (name "DA14") (class "Default")
      (node (ref "IC2") (pin "25") (pinfunction "25FB1MC7_25") (pintype "bidirectional"))
      (node (ref "ST1") (pin "65") (pinfunction "65_65") (pintype "passive"))
      (node (ref "X1") (pin "65") (pinfunction "65_65") (pintype "passive"))
    )
    (net (code "62") (name "DA15") (class "Default")
      (node (ref "IC2") (pin "28") (pinfunction "28FB1MC10_28") (pintype "bidirectional"))
      (node (ref "ST1") (pin "63") (pinfunction "63_63") (pintype "passive"))
      (node (ref "X1") (pin "63") (pinfunction "63_63") (pintype "passive"))
    )
    (net (code "63") (name "DG0") (class "Default")
      (node (ref "IC2") (pin "72") (pinfunction "72FB4MC4_72") (pintype "bidirectional"))
      (node (ref "IC3") (pin "82") (pinfunction "D8_82") (pintype "bidirectional"))
    )
    (net (code "64") (name "DG1") (class "Default")
      (node (ref "IC2") (pin "74") (pinfunction "74FB4MC11_74") (pintype "bidirectional"))
      (node (ref "IC3") (pin "81") (pinfunction "D9_81") (pintype "bidirectional"))
    )
    (net (code "65") (name "DG2") (class "Default")
      (node (ref "IC2") (pin "87") (pinfunction "87FB2MC1_87") (pintype "bidirectional"))
      (node (ref "IC3") (pin "80") (pinfunction "D10_80") (pintype "bidirectional"))
    )
    (net (code "66") (name "DG3") (class "Default")
      (node (ref "IC2") (pin "86") (pinfunction "86FB4MC16_86") (pintype "bidirectional"))
      (node (ref "IC3") (pin "79") (pinfunction "D11_79") (pintype "bidirectional"))
    )
    (net (code "67") (name "DG4") (class "Default")
      (node (ref "IC2") (pin "85") (pinfunction "85FB4MC13_85") (pintype "bidirectional"))
      (node (ref "IC3") (pin "78") (pinfunction "D12_78") (pintype "bidirectional"))
    )
    (net (code "68") (name "DG5") (class "Default")
      (node (ref "IC2") (pin "79") (pinfunction "79FB4MC18_79") (pintype "bidirectional"))
      (node (ref "IC3") (pin "76") (pinfunction "D13_76") (pintype "bidirectional"))
    )
    (net (code "69") (name "DG6") (class "Default")
      (node (ref "IC2") (pin "81") (pinfunction "81FB4MC10_81") (pintype "bidirectional"))
      (node (ref "IC3") (pin "75") (pinfunction "D14_75") (pintype "bidirectional"))
    )
    (net (code "70") (name "DG7") (class "Default")
      (node (ref "IC2") (pin "82") (pinfunction "82FB4MC12_82") (pintype "bidirectional"))
      (node (ref "IC3") (pin "74") (pinfunction "D15_74") (pintype "bidirectional"))
    )
    (net (code "71") (name "DG8") (class "Default")
      (node (ref "IC2") (pin "63") (pinfunction "63FB3MC13_63") (pintype "bidirectional"))
      (node (ref "IC3") (pin "92") (pinfunction "D0_92") (pintype "bidirectional"))
    )
    (net (code "72") (name "DG9") (class "Default")
      (node (ref "IC2") (pin "64") (pinfunction "64FB3MC16_64") (pintype "bidirectional"))
      (node (ref "IC3") (pin "91") (pinfunction "D1_91") (pintype "bidirectional"))
    )
    (net (code "73") (name "DG10") (class "Default")
      (node (ref "IC2") (pin "65") (pinfunction "65FB4MC1_65") (pintype "bidirectional"))
      (node (ref "IC3") (pin "90") (pinfunction "D2_90") (pintype "bidirectional"))
    )
    (net (code "74") (name "DG11") (class "Default")
      (node (ref "IC2") (pin "66") (pinfunction "66FB4MC9_66") (pintype "bidirectional"))
      (node (ref "IC3") (pin "89") (pinfunction "D3_89") (pintype "bidirectional"))
    )
    (net (code "75") (name "DG12") (class "Default")
      (node (ref "IC2") (pin "67") (pinfunction "67FB4MC2_67") (pintype "bidirectional"))
      (node (ref "IC3") (pin "88") (pinfunction "D4_88") (pintype "bidirectional"))
    )
    (net (code "76") (name "DG13") (class "Default")
      (node (ref "IC2") (pin "68") (pinfunction "68FB4MC5_68") (pintype "bidirectional"))
      (node (ref "IC3") (pin "87") (pinfunction "D5_87") (pintype "bidirectional"))
    )
    (net (code "77") (name "DG14") (class "Default")
      (node (ref "IC2") (pin "70") (pinfunction "70FB4MC8_70") (pintype "bidirectional"))
      (node (ref "IC3") (pin "85") (pinfunction "D6_85") (pintype "bidirectional"))
    )
    (net (code "78") (name "DG15") (class "Default")
      (node (ref "IC2") (pin "71") (pinfunction "71FB4MC3_71") (pintype "bidirectional"))
      (node (ref "IC3") (pin "84") (pinfunction "D7_84") (pintype "bidirectional"))
    )
    (net (code "79") (name "DOE") (class "Default")
      (node (ref "ST1") (pin "93") (pinfunction "93_93") (pintype "passive"))
    )
    (net (code "80") (name "E") (class "Default")
      (node (ref "ST1") (pin "50") (pinfunction "50_50") (pintype "passive"))
      (node (ref "X1") (pin "50") (pinfunction "50_50") (pintype "passive"))
    )
    (net (code "81") (name "FC0") (class "Default")
      (node (ref "ST1") (pin "31") (pinfunction "31_31") (pintype "passive"))
      (node (ref "X1") (pin "31") (pinfunction "31_31") (pintype "passive"))
    )
    (net (code "82") (name "FC1") (class "Default")
      (node (ref "ST1") (pin "33") (pinfunction "33_33") (pintype "passive"))
      (node (ref "X1") (pin "33") (pinfunction "33_33") (pintype "passive"))
    )
    (net (code "83") (name "FC2") (class "Default")
      (node (ref "ST1") (pin "35") (pinfunction "35_35") (pintype "passive"))
      (node (ref "X1") (pin "35") (pinfunction "35_35") (pintype "passive"))
    )
    (net (code "84") (name "GA") (class "Default")
      (node (ref "IC210") (pin "4") (pinfunction "2C_4") (pintype "bidirectional"))
      (node (ref "JP2") (pin "5") (pinfunction "5_5") (pintype "passive"))
    )
    (net (code "85") (name "GB") (class "Default")
      (node (ref "IC210") (pin "3") (pinfunction "2B_3") (pintype "bidirectional"))
      (node (ref "R40") (pin "2") (pinfunction "2_2") (pintype "passive"))
    )
    (net (code "86") (name "GG") (class "Default")
      (node (ref "IC3") (pin "101") (pinfunction "GREEN_101") (pintype "output"))
      (node (ref "R40") (pin "1") (pinfunction "1_1") (pintype "passive"))
      (node (ref "R41") (pin "2") (pinfunction "2_2") (pintype "passive"))
    )
    (net (code "87") (name "GND") (class "Default")
      (node (ref "C10") (pin "2") (pinfunction "2_2") (pintype "passive"))
      (node (ref "C11") (pin "1") (pinfunction "1_1") (pintype "passive"))
      (node (ref "C12") (pin "1") (pinfunction "1_1") (pintype "passive"))
      (node (ref "C13") (pin "2") (pinfunction "2_2") (pintype "passive"))
      (node (ref "C14") (pin "2") (pinfunction "2_2") (pintype "passive"))
      (node (ref "C15") (pin "1") (pinfunction "1_1") (pintype "passive"))
      (node (ref "C16") (pin "2") (pinfunction "2_2") (pintype "passive"))
      (node (ref "C17") (pin "1") (pinfunction "1_1") (pintype "passive"))
      (node (ref "C18") (pin "1") (pinfunction "1_1") (pintype "passive"))
      (node (ref "C19") (pin "2") (pinfunction "2_2") (pintype "passive"))
      (node (ref "C2") (pin "1") (pinfunction "1_1") (pintype "passive"))
      (node (ref "C20") (pin "2") (pinfunction "2_2") (pintype "passive"))
      (node (ref "C21") (pin "1") (pinfunction "1_1") (pintype "passive"))
      (node (ref "C22") (pin "1") (pinfunction "1_1") (pintype "passive"))
      (node (ref "C24") (pin "1") (pinfunction "1_1") (pintype "passive"))
      (node (ref "C25") (pin "1") (pinfunction "1_1") (pintype "passive"))
      (node (ref "C26") (pin "2") (pinfunction "2_2") (pintype "passive"))
      (node (ref "C27") (pin "2") (pinfunction "2_2") (pintype "passive"))
      (node (ref "C28") (pin "1") (pinfunction "1_1") (pintype "passive"))
      (node (ref "C29") (pin "2") (pinfunction "2_2") (pintype "passive"))
      (node (ref "C3") (pin "1") (pinfunction "1_1") (pintype "passive"))
      (node (ref "C30") (pin "2") (pinfunction "2_2") (pintype "passive"))
      (node (ref "C31") (pin "2") (pinfunction "2_2") (pintype "passive"))
      (node (ref "C32") (pin "2") (pinfunction "2_2") (pintype "passive"))
      (node (ref "C33") (pin "2") (pinfunction "2_2") (pintype "passive"))
      (node (ref "C34") (pin "2") (pinfunction "2_2") (pintype "passive"))
      (node (ref "C35") (pin "2") (pinfunction "2_2") (pintype "passive"))
      (node (ref "C36") (pin "2") (pinfunction "2_2") (pintype "passive"))
      (node (ref "C37") (pin "2") (pinfunction "2_2") (pintype "passive"))
      (node (ref "C4") (pin "1") (pinfunction "1_1") (pintype "passive"))
      (node (ref "C5") (pin "1") (pinfunction "1_1") (pintype "passive"))
      (node (ref "C6") (pin "1") (pinfunction "1_1") (pintype "passive"))
      (node (ref "C7") (pin "1") (pinfunction "1_1") (pintype "passive"))
      (node (ref "C9") (pin "2") (pinfunction "2_2") (pintype "passive"))
      (node (ref "D1") (pin "2") (pinfunction "K_2") (pintype "bidirectional"))
      (node (ref "IC1") (pin "1") (pinfunction "GND_1") (pintype "power_in"))
      (node (ref "IC11") (pin "3") (pinfunction "GND_3") (pintype "power_in"))
      (node (ref "IC12") (pin "3") (pinfunction "GND_3") (pintype "power_in"))
      (node (ref "IC2") (pin "100") (pinfunction "100GND_100") (pintype "bidirectional"))
      (node (ref "IC2") (pin "21") (pinfunction "21GND_21") (pintype "bidirectional"))
      (node (ref "IC2") (pin "31") (pinfunction "31GND_31") (pintype "bidirectional"))
      (node (ref "IC2") (pin "44") (pinfunction "44GND_44") (pintype "bidirectional"))
      (node (ref "IC2") (pin "62") (pinfunction "62GND_62") (pintype "bidirectional"))
      (node (ref "IC2") (pin "69") (pinfunction "69GND_69") (pintype "bidirectional"))
      (node (ref "IC2") (pin "75") (pinfunction "75GND_75") (pintype "bidirectional"))
      (node (ref "IC2") (pin "84") (pinfunction "84GND_84") (pintype "bidirectional"))
      (node (ref "IC210") (pin "15") (pinfunction "~{OE}_15") (pintype "input"))
      (node (ref "IC210") (pin "7") (pinfunction "4B_7") (pintype "bidirectional"))
      (node (ref "IC210") (pin "8") (pinfunction "4C_8") (pintype "bidirectional"))
      (node (ref "IC210") (pin "9") (pinfunction "GND_9") (pintype "power_in"))
      (node (ref "IC3") (pin "104") (pinfunction "VSS6_104") (pintype "power_in"))
      (node (ref "IC3") (pin "119") (pinfunction "AVSS3_119") (pintype "power_in"))
      (node (ref "IC3") (pin "124") (pinfunction "VSS7_124") (pintype "power_in"))
      (node (ref "IC3") (pin "136") (pinfunction "VSS8_136") (pintype "power_in"))
      (node (ref "IC3") (pin "15") (pinfunction "AVSS4_15") (pintype "power_in"))
      (node (ref "IC3") (pin "150") (pinfunction "VSS9_150") (pintype "power_in"))
      (node (ref "IC3") (pin "165") (pinfunction "VSS10_165") (pintype "power_in"))
      (node (ref "IC3") (pin "18") (pinfunction "VSS1_18") (pintype "power_in"))
      (node (ref "IC3") (pin "181") (pinfunction "VSS11_181") (pintype "power_in"))
      (node (ref "IC3") (pin "195") (pinfunction "VSS12_195") (pintype "power_in"))
      (node (ref "IC3") (pin "208") (pinfunction "VSS13_208") (pintype "power_in"))
      (node (ref "IC3") (pin "47") (pinfunction "AEN_47") (pintype "input"))
      (node (ref "IC3") (pin "48") (pinfunction "A22_48") (pintype "input"))
      (node (ref "IC3") (pin "50") (pinfunction "A23_50") (pintype "input"))
      (node (ref "IC3") (pin "52") (pinfunction "VSS2_52") (pintype "power_in"))
      (node (ref "IC3") (pin "67") (pinfunction "VSS3_67") (pintype "power_in"))
      (node (ref "IC3") (pin "77") (pinfunction "VSS4_77") (pintype "power_in"))
      (node (ref "IC3") (pin "86") (pinfunction "VSS5_86") (pintype "power_in"))
      (node (ref "IC3") (pin "93") (pinfunction "AVSS1_93") (pintype "power_in"))
      (node (ref "IC3") (pin "97") (pinfunction "AVSS2_97") (pintype "power_in"))
      (node (ref "IC4") (pin "27") (pinfunction "OE_27") (pintype "input"))
      (node (ref "IC5") (pin "27") (pinfunction "OE_27") (pintype "input"))
      (node (ref "IC6") (pin "27") (pinfunction "OE_27") (pintype "input"))
      (node (ref "IC7") (pin "27") (pinfunction "OE_27") (pintype "input"))
      (node (ref "IC9") (pin "P$2") (pinfunction "GND_P$2") (pintype "power_in"))
      (node (ref "JP1") (pin "10") (pinfunction "10_10") (pintype "passive"))
      (node (ref "JP1") (pin "2") (pinfunction "2_2") (pintype "passive"))
      (node (ref "R18") (pin "2") (pinfunction "P$2_2") (pintype "bidirectional"))
      (node (ref "R29") (pin "2") (pinfunction "2_2") (pintype "passive"))
      (node (ref "R3") (pin "2") (pinfunction "P$2_2") (pintype "bidirectional"))
      (node (ref "R32") (pin "2") (pinfunction "P$2_2") (pintype "bidirectional"))
      (node (ref "R39") (pin "1") (pinfunction "1_1") (pintype "passive"))
      (node (ref "R41") (pin "1") (pinfunction "1_1") (pintype "passive"))
      (node (ref "R43") (pin "1") (pinfunction "1_1") (pintype "passive"))
      (node (ref "R5") (pin "2") (pinfunction "P$2_2") (pintype "bidirectional"))
      (node (ref "SJ1") (pin "2") (pinfunction "2_2") (pintype "passive"))
      (node (ref "ST1") (pin "1") (pinfunction "1_1") (pintype "passive"))
      (node (ref "ST1") (pin "100") (pinfunction "100_100") (pintype "passive"))
      (node (ref "ST1") (pin "13") (pinfunction "13_13") (pintype "passive"))
      (node (ref "ST1") (pin "2") (pinfunction "2_2") (pintype "passive"))
      (node (ref "ST1") (pin "25") (pinfunction "25_25") (pintype "passive"))
      (node (ref "ST1") (pin "3") (pinfunction "3_3") (pintype "passive"))
      (node (ref "ST1") (pin "37") (pinfunction "37_37") (pintype "passive"))
      (node (ref "ST1") (pin "4") (pinfunction "4_4") (pintype "passive"))
      (node (ref "ST1") (pin "49") (pinfunction "49_49") (pintype "passive"))
      (node (ref "ST1") (pin "61") (pinfunction "61_61") (pintype "passive"))
      (node (ref "ST1") (pin "73") (pinfunction "73_73") (pintype "passive"))
      (node (ref "ST1") (pin "85") (pinfunction "85_85") (pintype "passive"))
      (node (ref "ST1") (pin "87") (pinfunction "87_87") (pintype "passive"))
      (node (ref "ST1") (pin "88") (pinfunction "88_88") (pintype "passive"))
      (node (ref "ST1") (pin "89") (pinfunction "89_89") (pintype "passive"))
      (node (ref "ST1") (pin "90") (pinfunction "90_90") (pintype "passive"))
      (node (ref "ST1") (pin "91") (pinfunction "91_91") (pintype "passive"))
      (node (ref "ST1") (pin "99") (pinfunction "99_99") (pintype "passive"))
      (node (ref "X1") (pin "1") (pinfunction "1_1") (pintype "passive"))
      (node (ref "X1") (pin "13") (pinfunction "13_13") (pintype "passive"))
      (node (ref "X1") (pin "2") (pinfunction "2_2") (pintype "passive"))
      (node (ref "X1") (pin "25") (pinfunction "25_25") (pintype "passive"))
      (node (ref "X1") (pin "3") (pinfunction "3_3") (pintype "passive"))
      (node (ref "X1") (pin "37") (pinfunction "37_37") (pintype "passive"))
      (node (ref "X1") (pin "4") (pinfunction "4_4") (pintype "passive"))
      (node (ref "X1") (pin "49") (pinfunction "49_49") (pintype "passive"))
      (node (ref "X1") (pin "61") (pinfunction "61_61") (pintype "passive"))
      (node (ref "X1") (pin "73") (pinfunction "73_73") (pintype "passive"))
      (node (ref "X1") (pin "85") (pinfunction "85_85") (pintype "passive"))
    )
    (net (code "88") (name "GNDA") (class "Default")
      (node (ref "JP2") (pin "1") (pinfunction "1_1") (pintype "passive"))
      (node (ref "JP2") (pin "10") (pinfunction "10_10") (pintype "passive"))
      (node (ref "JP2") (pin "2") (pinfunction "2_2") (pintype "passive"))
      (node (ref "JP2") (pin "9") (pinfunction "9_9") (pintype "passive"))
      (node (ref "R32") (pin "1") (pinfunction "P$1_1") (pintype "bidirectional"))
    )
    (net (code "89") (name "GO") (class "Default")
      (node (ref "FB6") (pin "1") (pinfunction "1_1") (pintype "passive"))
      (node (ref "IC210") (pin "12") (pinfunction "2A_12") (pintype "bidirectional"))
    )
    (net (code "90") (name "HA") (class "Default")
      (node (ref "IC12") (pin "6") (pinfunction "S2_6") (pintype "bidirectional"))
      (node (ref "JP2") (pin "13") (pinfunction "13_13") (pintype "passive"))
    )
    (net (code "91") (name "HB") (class "Default")
      (node (ref "C19") (pin "1") (pinfunction "1_1") (pintype "passive"))
      (node (ref "IC12") (pin "4") (pinfunction "S1_4") (pintype "bidirectional"))
      (node (ref "R37") (pin "2") (pinfunction "2_2") (pintype "passive"))
    )
    (net (code "92") (name "HO") (class "Default")
      (node (ref "FB9") (pin "1") (pinfunction "1_1") (pintype "passive"))
      (node (ref "IC12") (pin "5") (pinfunction "D_5") (pintype "bidirectional"))
    )
    (net (code "93") (name "HSYNC") (class "Default")
      (node (ref "IC3") (pin "98") (pinfunction "HSYNC_98") (pintype "output"))
      (node (ref "R37") (pin "1") (pinfunction "1_1") (pintype "passive"))
    )
    (net (code "94") (name "INCON2") (class "Default")
      (node (ref "IC2") (pin "59") (pinfunction "59FB3MC18_59") (pintype "bidirectional"))
      (node (ref "ST1") (pin "11") (pinfunction "11_11") (pintype "passive"))
      (node (ref "X1") (pin "11") (pinfunction "11_11") (pintype "passive"))
    )
    (net (code "95") (name "IO1") (class "Default")
      (node (ref "IC2") (pin "78") (pinfunction "78FB4MC14_78") (pintype "bidirectional"))
    )
    (net (code "96") (name "IO2") (class "Default")
      (node (ref "IC2") (pin "77") (pinfunction "77FB4MC7_77") (pintype "bidirectional"))
    )
    (net (code "97") (name "IO3") (class "Default")
      (node (ref "IC2") (pin "76") (pinfunction "76FB4MC6_76") (pintype "bidirectional"))
      (node (ref "SJ1") (pin "1") (pinfunction "1_1") (pintype "passive"))
    )
    (net (code "98") (name "IOR") (class "Default")
      (node (ref "IC2") (pin "91") (pinfunction "91FB2MC3_91") (pintype "bidirectional"))
      (node (ref "IC3") (pin "53") (pinfunction "IOR_53") (pintype "input"))
    )
    (net (code "99") (name "IORST") (class "Default")
      (node (ref "ST1") (pin "94") (pinfunction "94_94") (pintype "passive"))
    )
    (net (code "100") (name "IOW") (class "Default")
      (node (ref "IC2") (pin "95") (pinfunction "95FB2MC5_95") (pintype "bidirectional"))
      (node (ref "IC3") (pin "43") (pinfunction "IOW_43") (pintype "input"))
    )
    (net (code "101") (name "MCLK") (class "Default")
      (node (ref "IC2") (pin "22") (pinfunction "22FB1MC9-I/O/GCK1_22") (pintype "bidirectional"))
      (node (ref "R31") (pin "1") (pinfunction "1_1") (pintype "passive"))
    )
    (net (code "102") (name "MEMR") (class "Default")
      (node (ref "IC2") (pin "90") (pinfunction "90FB4MC17_90") (pintype "bidirectional"))
      (node (ref "IC3") (pin "66") (pinfunction "MEMR_66") (pintype "input"))
    )
    (net (code "103") (name "MEMW") (class "Default")
      (node (ref "IC2") (pin "89") (pinfunction "89FB4MC15_89") (pintype "bidirectional"))
      (node (ref "IC3") (pin "71") (pinfunction "MEMW_71") (pintype "input"))
    )
    (net (code "104") (name "MONISW") (class "Default")
      (node (ref "IC11") (pin "1") (pinfunction "S2/~{S1}_1") (pintype "input"))
      (node (ref "IC12") (pin "1") (pinfunction "S2/~{S1}_1") (pintype "input"))
      (node (ref "IC2") (pin "61") (pinfunction "61FB3MC12_61") (pintype "bidirectional"))
      (node (ref "IC210") (pin "14") (pinfunction "C/~{B}_14") (pintype "input"))
    )
    (net (code "105") (name "Net-(C1-Pad2)") (class "Default")
      (node (ref "C1") (pin "2") (pinfunction "2_2") (pintype "passive"))
      (node (ref "R26") (pin "2") (pinfunction "2_2") (pintype "passive"))
    )
    (net (code "106") (name "Net-(C10-Pad1)") (class "Default")
      (node (ref "C10") (pin "1") (pinfunction "1_1") (pintype "passive"))
      (node (ref "R27") (pin "2") (pinfunction "2_2") (pintype "passive"))
    )
    (net (code "107") (name "Net-(D1-A)") (class "Default")
      (node (ref "D1") (pin "1") (pinfunction "A_1") (pintype "bidirectional"))
      (node (ref "IC8") (pin "2") (pinfunction "V-_2") (pintype "passive"))
      (node (ref "IC8") (pin "3") (pinfunction "V-_3") (pintype "passive"))
      (node (ref "IC8") (pin "6") (pinfunction "V-_6") (pintype "passive"))
      (node (ref "IC8") (pin "7") (pinfunction "V-_7") (pintype "passive"))
      (node (ref "R30") (pin "2") (pinfunction "2_2") (pintype "passive"))
    )
    (net (code "108") (name "Net-(FB5-Pad2)") (class "Default")
      (node (ref "FB5") (pin "2") (pinfunction "2_2") (pintype "passive"))
      (node (ref "JP2") (pin "4") (pinfunction "4_4") (pintype "passive"))
    )
    (net (code "109") (name "Net-(FB6-Pad2)") (class "Default")
      (node (ref "FB6") (pin "2") (pinfunction "2_2") (pintype "passive"))
      (node (ref "JP2") (pin "6") (pinfunction "6_6") (pintype "passive"))
    )
    (net (code "110") (name "Net-(FB7-Pad2)") (class "Default")
      (node (ref "FB7") (pin "2") (pinfunction "2_2") (pintype "passive"))
      (node (ref "JP2") (pin "8") (pinfunction "8_8") (pintype "passive"))
    )
    (net (code "111") (name "Net-(FB8-Pad2)") (class "Default")
      (node (ref "FB8") (pin "2") (pinfunction "2_2") (pintype "passive"))
      (node (ref "JP2") (pin "12") (pinfunction "12_12") (pintype "passive"))
    )
    (net (code "112") (name "Net-(FB9-Pad2)") (class "Default")
      (node (ref "FB9") (pin "2") (pinfunction "2_2") (pintype "passive"))
      (node (ref "JP2") (pin "14") (pinfunction "14_14") (pintype "passive"))
    )
    (net (code "113") (name "Net-(IC2-83TDO)") (class "Default")
      (node (ref "IC2") (pin "83") (pinfunction "83TDO_83") (pintype "bidirectional"))
      (node (ref "R25") (pin "1") (pinfunction "1_1") (pintype "passive"))
    )
    (net (code "114") (name "Net-(IC3-AVDD1)") (class "Default")
      (node (ref "C26") (pin "1") (pinfunction "1_1") (pintype "passive"))
      (node (ref "IC3") (pin "95") (pinfunction "AVDD1_95") (pintype "power_in"))
      (node (ref "R28") (pin "1") (pinfunction "1_1") (pintype "passive"))
    )
    (net (code "115") (name "Net-(IC3-AVDD4)") (class "Default")
      (node (ref "C1") (pin "1") (pinfunction "1_1") (pintype "passive"))
      (node (ref "C12") (pin "2") (pinfunction "2_2") (pintype "passive"))
      (node (ref "C8") (pin "1") (pinfunction "1_1") (pintype "passive"))
      (node (ref "IC3") (pin "13") (pinfunction "AVDD4_13") (pintype "power_in"))
      (node (ref "R21") (pin "2") (pinfunction "2_2") (pintype "passive"))
    )
    (net (code "116") (name "Net-(IC3-CAS0)") (class "Default")
      (node (ref "IC3") (pin "4") (pinfunction "CAS0_4") (pintype "output"))
      (node (ref "R13") (pin "2") (pinfunction "P$2_2") (pintype "bidirectional"))
    )
    (net (code "117") (name "Net-(IC3-CAS1)") (class "Default")
      (node (ref "IC3") (pin "156") (pinfunction "CAS1_156") (pintype "output"))
      (node (ref "R14") (pin "2") (pinfunction "P$2_2") (pintype "bidirectional"))
    )
    (net (code "118") (name "Net-(IC3-CAS2)") (class "Default")
      (node (ref "IC3") (pin "145") (pinfunction "CAS2_145") (pintype "output"))
      (node (ref "R15") (pin "2") (pinfunction "P$2_2") (pintype "bidirectional"))
    )
    (net (code "119") (name "Net-(IC3-CAS3)") (class "Default")
      (node (ref "IC3") (pin "135") (pinfunction "CAS3_135") (pintype "output"))
      (node (ref "R16") (pin "2") (pinfunction "P$2_2") (pintype "bidirectional"))
    )
    (net (code "120") (name "Net-(IC3-CAS4)") (class "Default")
      (node (ref "IC3") (pin "3") (pinfunction "CAS4_3") (pintype "output"))
      (node (ref "R10") (pin "2") (pinfunction "P$2_2") (pintype "bidirectional"))
    )
    (net (code "121") (name "Net-(IC3-CAS5)") (class "Default")
      (node (ref "IC3") (pin "200") (pinfunction "CAS5_200") (pintype "output"))
      (node (ref "R11") (pin "2") (pinfunction "P$2_2") (pintype "bidirectional"))
    )
    (net (code "122") (name "Net-(IC3-CAS6)") (class "Default")
      (node (ref "IC3") (pin "179") (pinfunction "CAS6_179") (pintype "output"))
      (node (ref "R12") (pin "1") (pinfunction "P$1_1") (pintype "bidirectional"))
    )
    (net (code "123") (name "Net-(IC3-CAS7)") (class "Default")
      (node (ref "IC3") (pin "166") (pinfunction "CAS7_166") (pintype "output"))
      (node (ref "R4") (pin "P$8") (pinfunction "P$2_P$8") (pintype "bidirectional"))
    )
    (net (code "124") (name "Net-(IC3-IREF)") (class "Default")
      (node (ref "C23") (pin "2") (pinfunction "2_2") (pintype "passive"))
      (node (ref "IC3") (pin "103") (pinfunction "IREF_103") (pintype "input"))
      (node (ref "IC8") (pin "4") (pinfunction "V+_4") (pintype "passive"))
    )
    (net (code "125") (name "Net-(IC3-MA0)") (class "Default")
      (node (ref "IC3") (pin "180") (pinfunction "MA0_180") (pintype "output"))
      (node (ref "R1") (pin "P$8") (pinfunction "P$2_P$8") (pintype "bidirectional"))
    )
    (net (code "126") (name "Net-(IC3-MA1)") (class "Default")
      (node (ref "IC3") (pin "182") (pinfunction "MA1_182") (pintype "output"))
      (node (ref "R1") (pin "P$7") (pinfunction "P$2_P$7") (pintype "bidirectional"))
    )
    (net (code "127") (name "Net-(IC3-MA2)") (class "Default")
      (node (ref "IC3") (pin "183") (pinfunction "MA2_183") (pintype "output"))
      (node (ref "R1") (pin "P$6") (pinfunction "P$2_P$6") (pintype "bidirectional"))
    )
    (net (code "128") (name "Net-(IC3-MA3)") (class "Default")
      (node (ref "IC3") (pin "184") (pinfunction "MA3_184") (pintype "output"))
      (node (ref "R1") (pin "P$5") (pinfunction "P$2_P$5") (pintype "bidirectional"))
    )
    (net (code "129") (name "Net-(IC3-MA4)") (class "Default")
      (node (ref "IC3") (pin "185") (pinfunction "MA4_185") (pintype "output"))
      (node (ref "R9") (pin "2") (pinfunction "P$2_2") (pintype "bidirectional"))
    )
    (net (code "130") (name "Net-(IC3-MA5)") (class "Default")
      (node (ref "IC3") (pin "186") (pinfunction "MA5_186") (pintype "output"))
      (node (ref "R2") (pin "P$8") (pinfunction "P$2_P$8") (pintype "bidirectional"))
    )
    (net (code "131") (name "Net-(IC3-MA6)") (class "Default")
      (node (ref "IC3") (pin "187") (pinfunction "MA6_187") (pintype "output"))
      (node (ref "R2") (pin "P$7") (pinfunction "P$2_P$7") (pintype "bidirectional"))
    )
    (net (code "132") (name "Net-(IC3-MA7)") (class "Default")
      (node (ref "IC3") (pin "188") (pinfunction "MA7_188") (pintype "output"))
      (node (ref "R2") (pin "P$6") (pinfunction "P$2_P$6") (pintype "bidirectional"))
    )
    (net (code "133") (name "Net-(IC3-MA8)") (class "Default")
      (node (ref "IC3") (pin "189") (pinfunction "MA8_189") (pintype "output"))
      (node (ref "R2") (pin "P$5") (pinfunction "P$2_P$5") (pintype "bidirectional"))
    )
    (net (code "134") (name "Net-(IC3-MCLK)") (class "Default")
      (node (ref "IC3") (pin "16") (pinfunction "MCLK_16") (pintype "bidirectional"))
      (node (ref "R31") (pin "2") (pinfunction "2_2") (pintype "passive"))
    )
    (net (code "135") (name "Net-(IC3-MFILTER)") (class "Default")
      (node (ref "C8") (pin "2") (pinfunction "2_2") (pintype "passive"))
      (node (ref "IC3") (pin "14") (pinfunction "MFILTER_14") (pintype "input"))
      (node (ref "R26") (pin "1") (pinfunction "1_1") (pintype "passive"))
    )
    (net (code "136") (name "Net-(IC3-RAS1)") (class "Default")
      (node (ref "IC3") (pin "168") (pinfunction "RAS1_168") (pintype "output"))
      (node (ref "R4") (pin "P$6") (pinfunction "P$2_P$6") (pintype "bidirectional"))
    )
    (net (code "137") (name "Net-(IC3-RESET)") (class "Default")
      (node (ref "IC3") (pin "51") (pinfunction "RESET_51") (pintype "input"))
      (node (ref "R20") (pin "2") (pinfunction "2_2") (pintype "passive"))
    )
    (net (code "138") (name "Net-(IC3-TWR)") (class "Default")
      (node (ref "IC3") (pin "105") (pinfunction "TWR_105") (pintype "input"))
      (node (ref "R19") (pin "2") (pinfunction "2_2") (pintype "passive"))
    )
    (net (code "139") (name "Net-(IC3-VFILTER)") (class "Default")
      (node (ref "C9") (pin "1") (pinfunction "1_1") (pintype "passive"))
      (node (ref "IC3") (pin "94") (pinfunction "VFILTER_94") (pintype "input"))
      (node (ref "R27") (pin "1") (pinfunction "1_1") (pintype "passive"))
    )
    (net (code "140") (name "Net-(IC3-WE)") (class "Default")
      (node (ref "IC3") (pin "167") (pinfunction "WE_167") (pintype "output"))
      (node (ref "R4") (pin "P$7") (pinfunction "P$2_P$7") (pintype "bidirectional"))
    )
    (net (code "141") (name "Net-(IC8-R)") (class "Default")
      (node (ref "IC8") (pin "1") (pinfunction "R_1") (pintype "passive"))
      (node (ref "R29") (pin "1") (pinfunction "1_1") (pintype "passive"))
      (node (ref "R30") (pin "1") (pinfunction "1_1") (pintype "passive"))
    )
    (net (code "142") (name "Net-(IC9-OUT)") (class "Default")
      (node (ref "IC9") (pin "P$3") (pinfunction "OUT_P$3") (pintype "output"))
      (node (ref "R17") (pin "1") (pinfunction "1_1") (pintype "passive"))
    )
    (net (code "143") (name "Net-(IC9-TRI)") (class "Default")
      (node (ref "C33") (pin "1") (pinfunction "1_1") (pintype "passive"))
      (node (ref "FB1") (pin "2") (pinfunction "2_2") (pintype "passive"))
      (node (ref "IC9") (pin "P$1") (pinfunction "TRI_P$1") (pintype "input"))
      (node (ref "IC9") (pin "P$4") (pinfunction "VDD_P$4") (pintype "power_in"))
    )
    (net (code "144") (name "Net-(IC11-VCC)") (class "Default")
      (node (ref "C29") (pin "1") (pinfunction "1_1") (pintype "passive"))
      (node (ref "FB3") (pin "1") (pinfunction "1_1") (pintype "passive"))
      (node (ref "IC11") (pin "2") (pinfunction "VCC_2") (pintype "power_in"))
    )
    (net (code "145") (name "Net-(IC12-VCC)") (class "Default")
      (node (ref "C31") (pin "1") (pinfunction "1_1") (pintype "passive"))
      (node (ref "FB4") (pin "1") (pinfunction "1_1") (pintype "passive"))
      (node (ref "IC12") (pin "2") (pinfunction "VCC_2") (pintype "power_in"))
    )
    (net (code "146") (name "Net-(IC210-VCC)") (class "Default")
      (node (ref "C16") (pin "1") (pinfunction "1_1") (pintype "passive"))
      (node (ref "FB2") (pin "1") (pinfunction "1_1") (pintype "passive"))
      (node (ref "IC210") (pin "16") (pinfunction "VCC_16") (pintype "power_in"))
    )
    (net (code "147") (name "OCLK") (class "Default")
      (node (ref "IC3") (pin "17") (pinfunction "OSC_17") (pintype "input"))
      (node (ref "R17") (pin "2") (pinfunction "2_2") (pintype "passive"))
    )
    (net (code "148") (name "RA") (class "Default")
      (node (ref "IC210") (pin "2") (pinfunction "1C_2") (pintype "bidirectional"))
      (node (ref "JP2") (pin "3") (pinfunction "3_3") (pintype "passive"))
    )
    (net (code "149") (name "RA0") (class "Default")
      (node (ref "IC4") (pin "16") (pinfunction "A0_16") (pintype "input"))
      (node (ref "IC5") (pin "16") (pinfunction "A0_16") (pintype "input"))
      (node (ref "IC6") (pin "16") (pinfunction "A0_16") (pintype "input"))
      (node (ref "IC7") (pin "16") (pinfunction "A0_16") (pintype "input"))
      (node (ref "R1") (pin "P$1") (pinfunction "P$1_P$1") (pintype "bidirectional"))
    )
    (net (code "150") (name "RA1") (class "Default")
      (node (ref "IC4") (pin "17") (pinfunction "A1_17") (pintype "input"))
      (node (ref "IC5") (pin "17") (pinfunction "A1_17") (pintype "input"))
      (node (ref "IC6") (pin "17") (pinfunction "A1_17") (pintype "input"))
      (node (ref "IC7") (pin "17") (pinfunction "A1_17") (pintype "input"))
      (node (ref "R1") (pin "P$2") (pinfunction "P$1_P$2") (pintype "bidirectional"))
    )
    (net (code "151") (name "RA2") (class "Default")
      (node (ref "IC4") (pin "18") (pinfunction "A2_18") (pintype "input"))
      (node (ref "IC5") (pin "18") (pinfunction "A2_18") (pintype "input"))
      (node (ref "IC6") (pin "18") (pinfunction "A2_18") (pintype "input"))
      (node (ref "IC7") (pin "18") (pinfunction "A2_18") (pintype "input"))
      (node (ref "R1") (pin "P$3") (pinfunction "P$1_P$3") (pintype "bidirectional"))
    )
    (net (code "152") (name "RA3") (class "Default")
      (node (ref "IC4") (pin "19") (pinfunction "A3_19") (pintype "input"))
      (node (ref "IC5") (pin "19") (pinfunction "A3_19") (pintype "input"))
      (node (ref "IC6") (pin "19") (pinfunction "A3_19") (pintype "input"))
      (node (ref "IC7") (pin "19") (pinfunction "A3_19") (pintype "input"))
      (node (ref "R1") (pin "P$4") (pinfunction "P$1_P$4") (pintype "bidirectional"))
    )
    (net (code "153") (name "RA4") (class "Default")
      (node (ref "IC4") (pin "22") (pinfunction "A4_22") (pintype "input"))
      (node (ref "IC5") (pin "22") (pinfunction "A4_22") (pintype "input"))
      (node (ref "IC6") (pin "22") (pinfunction "A4_22") (pintype "input"))
      (node (ref "IC7") (pin "22") (pinfunction "A4_22") (pintype "input"))
      (node (ref "R9") (pin "1") (pinfunction "P$1_1") (pintype "bidirectional"))
    )
    (net (code "154") (name "RA5") (class "Default")
      (node (ref "IC4") (pin "23") (pinfunction "A5_23") (pintype "input"))
      (node (ref "IC5") (pin "23") (pinfunction "A5_23") (pintype "input"))
      (node (ref "IC6") (pin "23") (pinfunction "A5_23") (pintype "input"))
      (node (ref "IC7") (pin "23") (pinfunction "A5_23") (pintype "input"))
      (node (ref "R2") (pin "P$1") (pinfunction "P$1_P$1") (pintype "bidirectional"))
    )
    (net (code "155") (name "RA6") (class "Default")
      (node (ref "IC4") (pin "24") (pinfunction "A6_24") (pintype "input"))
      (node (ref "IC5") (pin "24") (pinfunction "A6_24") (pintype "input"))
      (node (ref "IC6") (pin "24") (pinfunction "A6_24") (pintype "input"))
      (node (ref "IC7") (pin "24") (pinfunction "A6_24") (pintype "input"))
      (node (ref "R2") (pin "P$2") (pinfunction "P$1_P$2") (pintype "bidirectional"))
    )
    (net (code "156") (name "RA7") (class "Default")
      (node (ref "IC4") (pin "25") (pinfunction "A7_25") (pintype "input"))
      (node (ref "IC5") (pin "25") (pinfunction "A7_25") (pintype "input"))
      (node (ref "IC6") (pin "25") (pinfunction "A7_25") (pintype "input"))
      (node (ref "IC7") (pin "25") (pinfunction "A7_25") (pintype "input"))
      (node (ref "R2") (pin "P$3") (pinfunction "P$1_P$3") (pintype "bidirectional"))
    )
    (net (code "157") (name "RA8") (class "Default")
      (node (ref "IC4") (pin "26") (pinfunction "A8_26") (pintype "input"))
      (node (ref "IC5") (pin "26") (pinfunction "A8_26") (pintype "input"))
      (node (ref "IC6") (pin "26") (pinfunction "A8_26") (pintype "input"))
      (node (ref "IC7") (pin "26") (pinfunction "A8_26") (pintype "input"))
      (node (ref "R2") (pin "P$4") (pinfunction "P$1_P$4") (pintype "bidirectional"))
    )
    (net (code "158") (name "RAS0") (class "Default")
      (node (ref "R4") (pin "P$4") (pinfunction "P$1_P$4") (pintype "bidirectional"))
    )
    (net (code "159") (name "RAS1") (class "Default")
      (node (ref "IC4") (pin "14") (pinfunction "RAS_14") (pintype "input"))
      (node (ref "IC5") (pin "14") (pinfunction "RAS_14") (pintype "input"))
      (node (ref "IC6") (pin "14") (pinfunction "RAS_14") (pintype "input"))
      (node (ref "IC7") (pin "14") (pinfunction "RAS_14") (pintype "input"))
      (node (ref "R4") (pin "P$3") (pinfunction "P$1_P$3") (pintype "bidirectional"))
    )
    (net (code "160") (name "RB") (class "Default")
      (node (ref "IC210") (pin "1") (pinfunction "1B_1") (pintype "bidirectional"))
      (node (ref "R42") (pin "2") (pinfunction "2_2") (pintype "passive"))
    )
    (net (code "161") (name "RD0") (class "Default")
      (node (ref "IC3") (pin "12") (pinfunction "MD0_12") (pintype "bidirectional"))
      (node (ref "IC4") (pin "39") (pinfunction "DQ15_39") (pintype "bidirectional"))
    )
    (net (code "162") (name "RD1") (class "Default")
      (node (ref "IC3") (pin "11") (pinfunction "MD1_11") (pintype "bidirectional"))
      (node (ref "IC4") (pin "38") (pinfunction "DQ14_38") (pintype "bidirectional"))
    )
    (net (code "163") (name "RD2") (class "Default")
      (node (ref "IC3") (pin "10") (pinfunction "MD2_10") (pintype "bidirectional"))
      (node (ref "IC4") (pin "37") (pinfunction "DQ13_37") (pintype "bidirectional"))
    )
    (net (code "164") (name "RD3") (class "Default")
      (node (ref "IC3") (pin "9") (pinfunction "MD3_9") (pintype "bidirectional"))
      (node (ref "IC4") (pin "36") (pinfunction "DQ12_36") (pintype "bidirectional"))
    )
    (net (code "165") (name "RD4") (class "Default")
      (node (ref "IC3") (pin "8") (pinfunction "MD4_8") (pintype "bidirectional"))
      (node (ref "IC4") (pin "34") (pinfunction "DQ11_34") (pintype "bidirectional"))
    )
    (net (code "166") (name "RD5") (class "Default")
      (node (ref "IC3") (pin "7") (pinfunction "MD5_7") (pintype "bidirectional"))
      (node (ref "IC4") (pin "33") (pinfunction "DQ10_33") (pintype "bidirectional"))
    )
    (net (code "167") (name "RD6") (class "Default")
      (node (ref "IC3") (pin "6") (pinfunction "MD6_6") (pintype "bidirectional"))
      (node (ref "IC4") (pin "32") (pinfunction "DQ9_32") (pintype "bidirectional"))
    )
    (net (code "168") (name "RD7") (class "Default")
      (node (ref "IC3") (pin "5") (pinfunction "MD7_5") (pintype "bidirectional"))
      (node (ref "IC4") (pin "31") (pinfunction "DQ8_31") (pintype "bidirectional"))
    )
    (net (code "169") (name "RD8") (class "Default")
      (node (ref "IC3") (pin "155") (pinfunction "MD8_155") (pintype "bidirectional"))
      (node (ref "IC7") (pin "2") (pinfunction "DQ0_2") (pintype "bidirectional"))
    )
    (net (code "170") (name "RD9") (class "Default")
      (node (ref "IC3") (pin "154") (pinfunction "MD9_154") (pintype "bidirectional"))
      (node (ref "IC7") (pin "3") (pinfunction "DQ1_3") (pintype "bidirectional"))
    )
    (net (code "171") (name "RD10") (class "Default")
      (node (ref "IC3") (pin "153") (pinfunction "MD10_153") (pintype "bidirectional"))
      (node (ref "IC7") (pin "4") (pinfunction "DQ2_4") (pintype "bidirectional"))
    )
    (net (code "172") (name "RD11") (class "Default")
      (node (ref "IC3") (pin "152") (pinfunction "MD11_152") (pintype "bidirectional"))
      (node (ref "IC7") (pin "5") (pinfunction "DQ3_5") (pintype "bidirectional"))
    )
    (net (code "173") (name "RD12") (class "Default")
      (node (ref "IC3") (pin "151") (pinfunction "MD12_151") (pintype "bidirectional"))
      (node (ref "IC7") (pin "7") (pinfunction "DQ4_7") (pintype "bidirectional"))
    )
    (net (code "174") (name "RD13") (class "Default")
      (node (ref "IC3") (pin "149") (pinfunction "MD13_149") (pintype "bidirectional"))
      (node (ref "IC7") (pin "8") (pinfunction "DQ5_8") (pintype "bidirectional"))
    )
    (net (code "175") (name "RD14") (class "Default")
      (node (ref "IC3") (pin "148") (pinfunction "MD14_148") (pintype "bidirectional"))
      (node (ref "IC7") (pin "9") (pinfunction "DQ6_9") (pintype "bidirectional"))
    )
    (net (code "176") (name "RD15") (class "Default")
      (node (ref "IC3") (pin "147") (pinfunction "MD15_147") (pintype "bidirectional"))
      (node (ref "IC7") (pin "10") (pinfunction "DQ7_10") (pintype "bidirectional"))
    )
    (net (code "177") (name "RD16") (class "Default")
      (node (ref "IC3") (pin "144") (pinfunction "MD16_144") (pintype "bidirectional"))
      (node (ref "IC5") (pin "39") (pinfunction "DQ15_39") (pintype "bidirectional"))
    )
    (net (code "178") (name "RD17") (class "Default")
      (node (ref "IC3") (pin "143") (pinfunction "MD17_143") (pintype "bidirectional"))
      (node (ref "IC5") (pin "38") (pinfunction "DQ14_38") (pintype "bidirectional"))
    )
    (net (code "179") (name "RD18") (class "Default")
      (node (ref "IC3") (pin "142") (pinfunction "MD18_142") (pintype "bidirectional"))
      (node (ref "IC5") (pin "37") (pinfunction "DQ13_37") (pintype "bidirectional"))
    )
    (net (code "180") (name "RD19") (class "Default")
      (node (ref "IC3") (pin "141") (pinfunction "MD19_141") (pintype "bidirectional"))
      (node (ref "IC5") (pin "36") (pinfunction "DQ12_36") (pintype "bidirectional"))
    )
    (net (code "181") (name "RD20") (class "Default")
      (node (ref "IC3") (pin "140") (pinfunction "MD20_140") (pintype "bidirectional"))
      (node (ref "IC5") (pin "34") (pinfunction "DQ11_34") (pintype "bidirectional"))
    )
    (net (code "182") (name "RD21") (class "Default")
      (node (ref "IC3") (pin "139") (pinfunction "MD21_139") (pintype "bidirectional"))
      (node (ref "IC5") (pin "33") (pinfunction "DQ10_33") (pintype "bidirectional"))
    )
    (net (code "183") (name "RD22") (class "Default")
      (node (ref "IC3") (pin "138") (pinfunction "MD22_138") (pintype "bidirectional"))
      (node (ref "IC5") (pin "32") (pinfunction "DQ9_32") (pintype "bidirectional"))
    )
    (net (code "184") (name "RD23") (class "Default")
      (node (ref "IC3") (pin "137") (pinfunction "MD23_137") (pintype "bidirectional"))
      (node (ref "IC5") (pin "31") (pinfunction "DQ8_31") (pintype "bidirectional"))
    )
    (net (code "185") (name "RD24") (class "Default")
      (node (ref "IC3") (pin "134") (pinfunction "MD24_134") (pintype "bidirectional"))
      (node (ref "IC5") (pin "2") (pinfunction "DQ0_2") (pintype "bidirectional"))
    )
    (net (code "186") (name "RD25") (class "Default")
      (node (ref "IC3") (pin "133") (pinfunction "MD25_133") (pintype "bidirectional"))
      (node (ref "IC5") (pin "3") (pinfunction "DQ1_3") (pintype "bidirectional"))
    )
    (net (code "187") (name "RD26") (class "Default")
      (node (ref "IC3") (pin "132") (pinfunction "MD26_132") (pintype "bidirectional"))
      (node (ref "IC5") (pin "4") (pinfunction "DQ2_4") (pintype "bidirectional"))
    )
    (net (code "188") (name "RD27") (class "Default")
      (node (ref "IC3") (pin "131") (pinfunction "MD27_131") (pintype "bidirectional"))
      (node (ref "IC5") (pin "5") (pinfunction "DQ3_5") (pintype "bidirectional"))
    )
    (net (code "189") (name "RD28") (class "Default")
      (node (ref "IC3") (pin "130") (pinfunction "MD28_130") (pintype "bidirectional"))
      (node (ref "IC5") (pin "7") (pinfunction "DQ4_7") (pintype "bidirectional"))
    )
    (net (code "190") (name "RD29") (class "Default")
      (node (ref "IC3") (pin "129") (pinfunction "MD29_129") (pintype "bidirectional"))
      (node (ref "IC5") (pin "8") (pinfunction "DQ5_8") (pintype "bidirectional"))
    )
    (net (code "191") (name "RD30") (class "Default")
      (node (ref "IC3") (pin "128") (pinfunction "MD30_128") (pintype "bidirectional"))
      (node (ref "IC5") (pin "9") (pinfunction "DQ6_9") (pintype "bidirectional"))
    )
    (net (code "192") (name "RD31") (class "Default")
      (node (ref "IC3") (pin "127") (pinfunction "MD31_127") (pintype "bidirectional"))
      (node (ref "IC5") (pin "10") (pinfunction "DQ7_10") (pintype "bidirectional"))
    )
    (net (code "193") (name "RD32") (class "Default")
      (node (ref "IC3") (pin "2") (pinfunction "MD32_2") (pintype "bidirectional"))
      (node (ref "IC4") (pin "2") (pinfunction "DQ0_2") (pintype "bidirectional"))
    )
    (net (code "194") (name "RD33") (class "Default")
      (node (ref "IC3") (pin "207") (pinfunction "MD33_207") (pintype "bidirectional"))
      (node (ref "IC4") (pin "3") (pinfunction "DQ1_3") (pintype "bidirectional"))
    )
    (net (code "195") (name "RD34") (class "Default")
      (node (ref "IC3") (pin "206") (pinfunction "MD34_206") (pintype "bidirectional"))
      (node (ref "IC4") (pin "4") (pinfunction "DQ2_4") (pintype "bidirectional"))
    )
    (net (code "196") (name "RD35") (class "Default")
      (node (ref "IC3") (pin "205") (pinfunction "MD35_205") (pintype "bidirectional"))
      (node (ref "IC4") (pin "5") (pinfunction "DQ3_5") (pintype "bidirectional"))
    )
    (net (code "197") (name "RD36") (class "Default")
      (node (ref "IC3") (pin "204") (pinfunction "MD36_204") (pintype "bidirectional"))
      (node (ref "IC4") (pin "7") (pinfunction "DQ4_7") (pintype "bidirectional"))
    )
    (net (code "198") (name "RD37") (class "Default")
      (node (ref "IC3") (pin "203") (pinfunction "MD37_203") (pintype "bidirectional"))
      (node (ref "IC4") (pin "8") (pinfunction "DQ5_8") (pintype "bidirectional"))
    )
    (net (code "199") (name "RD38") (class "Default")
      (node (ref "IC3") (pin "202") (pinfunction "MD38_202") (pintype "bidirectional"))
      (node (ref "IC4") (pin "9") (pinfunction "DQ6_9") (pintype "bidirectional"))
    )
    (net (code "200") (name "RD39") (class "Default")
      (node (ref "IC3") (pin "201") (pinfunction "MD39_201") (pintype "bidirectional"))
      (node (ref "IC4") (pin "10") (pinfunction "DQ7_10") (pintype "bidirectional"))
    )
    (net (code "201") (name "RD40") (class "Default")
      (node (ref "IC3") (pin "199") (pinfunction "MD40_199") (pintype "bidirectional"))
      (node (ref "IC6") (pin "39") (pinfunction "DQ15_39") (pintype "bidirectional"))
    )
    (net (code "202") (name "RD41") (class "Default")
      (node (ref "IC3") (pin "198") (pinfunction "MD41_198") (pintype "bidirectional"))
      (node (ref "IC6") (pin "38") (pinfunction "DQ14_38") (pintype "bidirectional"))
    )
    (net (code "203") (name "RD42") (class "Default")
      (node (ref "IC3") (pin "197") (pinfunction "MD42_197") (pintype "bidirectional"))
      (node (ref "IC6") (pin "37") (pinfunction "DQ13_37") (pintype "bidirectional"))
    )
    (net (code "204") (name "RD43") (class "Default")
      (node (ref "IC3") (pin "196") (pinfunction "MD43_196") (pintype "bidirectional"))
      (node (ref "IC6") (pin "36") (pinfunction "DQ12_36") (pintype "bidirectional"))
    )
    (net (code "205") (name "RD44") (class "Default")
      (node (ref "IC3") (pin "194") (pinfunction "MD44_194") (pintype "bidirectional"))
      (node (ref "IC6") (pin "34") (pinfunction "DQ11_34") (pintype "bidirectional"))
    )
    (net (code "206") (name "RD45") (class "Default")
      (node (ref "IC3") (pin "193") (pinfunction "MD45_193") (pintype "bidirectional"))
      (node (ref "IC6") (pin "33") (pinfunction "DQ10_33") (pintype "bidirectional"))
    )
    (net (code "207") (name "RD46") (class "Default")
      (node (ref "IC3") (pin "192") (pinfunction "MD46_192") (pintype "bidirectional"))
      (node (ref "IC6") (pin "32") (pinfunction "DQ9_32") (pintype "bidirectional"))
    )
    (net (code "208") (name "RD47") (class "Default")
      (node (ref "IC3") (pin "191") (pinfunction "MD47_191") (pintype "bidirectional"))
      (node (ref "IC6") (pin "31") (pinfunction "DQ8_31") (pintype "bidirectional"))
    )
    (net (code "209") (name "RD48") (class "Default")
      (node (ref "IC3") (pin "177") (pinfunction "MD48_177") (pintype "bidirectional"))
      (node (ref "IC6") (pin "2") (pinfunction "DQ0_2") (pintype "bidirectional"))
    )
    (net (code "210") (name "RD49") (class "Default")
      (node (ref "IC3") (pin "176") (pinfunction "MD49_176") (pintype "bidirectional"))
      (node (ref "IC6") (pin "3") (pinfunction "DQ1_3") (pintype "bidirectional"))
    )
    (net (code "211") (name "RD50") (class "Default")
      (node (ref "IC3") (pin "175") (pinfunction "MD50_175") (pintype "bidirectional"))
      (node (ref "IC6") (pin "4") (pinfunction "DQ2_4") (pintype "bidirectional"))
    )
    (net (code "212") (name "RD51") (class "Default")
      (node (ref "IC3") (pin "174") (pinfunction "MD51_174") (pintype "bidirectional"))
      (node (ref "IC6") (pin "5") (pinfunction "DQ3_5") (pintype "bidirectional"))
    )
    (net (code "213") (name "RD52") (class "Default")
      (node (ref "IC3") (pin "173") (pinfunction "MD52_173") (pintype "bidirectional"))
      (node (ref "IC6") (pin "7") (pinfunction "DQ4_7") (pintype "bidirectional"))
    )
    (net (code "214") (name "RD53") (class "Default")
      (node (ref "IC3") (pin "172") (pinfunction "MD53_172") (pintype "bidirectional"))
      (node (ref "IC6") (pin "8") (pinfunction "DQ5_8") (pintype "bidirectional"))
    )
    (net (code "215") (name "RD54") (class "Default")
      (node (ref "IC3") (pin "171") (pinfunction "MD54_171") (pintype "bidirectional"))
      (node (ref "IC6") (pin "9") (pinfunction "DQ6_9") (pintype "bidirectional"))
    )
    (net (code "216") (name "RD55") (class "Default")
      (node (ref "IC3") (pin "170") (pinfunction "MD55_170") (pintype "bidirectional"))
      (node (ref "IC6") (pin "10") (pinfunction "DQ7_10") (pintype "bidirectional"))
    )
    (net (code "217") (name "RD56") (class "Default")
      (node (ref "IC3") (pin "164") (pinfunction "MD56_164") (pintype "bidirectional"))
      (node (ref "IC7") (pin "39") (pinfunction "DQ15_39") (pintype "bidirectional"))
      (node (ref "R3") (pin "1") (pinfunction "P$1_1") (pintype "bidirectional"))
    )
    (net (code "218") (name "RD57") (class "Default")
      (node (ref "IC3") (pin "163") (pinfunction "MD57_163") (pintype "bidirectional"))
      (node (ref "IC7") (pin "38") (pinfunction "DQ14_38") (pintype "bidirectional"))
      (node (ref "R5") (pin "1") (pinfunction "P$1_1") (pintype "bidirectional"))
    )
    (net (code "219") (name "RD58") (class "Default")
      (node (ref "IC3") (pin "162") (pinfunction "MD58_162") (pintype "bidirectional"))
      (node (ref "IC7") (pin "37") (pinfunction "DQ13_37") (pintype "bidirectional"))
      (node (ref "R18") (pin "1") (pinfunction "P$1_1") (pintype "bidirectional"))
    )
    (net (code "220") (name "RD59") (class "Default")
      (node (ref "IC3") (pin "161") (pinfunction "MD59_161") (pintype "bidirectional"))
      (node (ref "IC7") (pin "36") (pinfunction "DQ12_36") (pintype "bidirectional"))
    )
    (net (code "221") (name "RD60") (class "Default")
      (node (ref "IC3") (pin "160") (pinfunction "MD60_160") (pintype "bidirectional"))
      (node (ref "IC7") (pin "34") (pinfunction "DQ11_34") (pintype "bidirectional"))
    )
    (net (code "222") (name "RD61") (class "Default")
      (node (ref "IC3") (pin "159") (pinfunction "MD61_159") (pintype "bidirectional"))
      (node (ref "IC7") (pin "33") (pinfunction "DQ10_33") (pintype "bidirectional"))
    )
    (net (code "223") (name "RD62") (class "Default")
      (node (ref "IC3") (pin "158") (pinfunction "MD62_158") (pintype "bidirectional"))
      (node (ref "IC7") (pin "32") (pinfunction "DQ9_32") (pintype "bidirectional"))
    )
    (net (code "224") (name "RD63") (class "Default")
      (node (ref "IC3") (pin "157") (pinfunction "MD63_157") (pintype "bidirectional"))
      (node (ref "IC7") (pin "31") (pinfunction "DQ8_31") (pintype "bidirectional"))
    )
    (net (code "225") (name "RG") (class "Default")
      (node (ref "IC3") (pin "102") (pinfunction "RED_102") (pintype "output"))
      (node (ref "R42") (pin "1") (pinfunction "1_1") (pintype "passive"))
      (node (ref "R43") (pin "2") (pinfunction "2_2") (pintype "passive"))
    )
    (net (code "226") (name "RO") (class "Default")
      (node (ref "FB5") (pin "1") (pinfunction "1_1") (pintype "passive"))
      (node (ref "IC210") (pin "13") (pinfunction "1A_13") (pintype "bidirectional"))
    )
    (net (code "227") (name "RWE") (class "Default")
      (node (ref "IC4") (pin "13") (pinfunction "WE_13") (pintype "input"))
      (node (ref "IC5") (pin "13") (pinfunction "WE_13") (pintype "input"))
      (node (ref "IC6") (pin "13") (pinfunction "WE_13") (pintype "input"))
      (node (ref "IC7") (pin "13") (pinfunction "WE_13") (pintype "input"))
      (node (ref "R4") (pin "P$2") (pinfunction "P$1_P$2") (pintype "bidirectional"))
    )
    (net (code "228") (name "R{slash}W") (class "Default")
      (node (ref "IC2") (pin "24") (pinfunction "24N.C._24") (pintype "bidirectional"))
      (node (ref "ST1") (pin "68") (pinfunction "68_68") (pintype "passive"))
      (node (ref "X1") (pin "68") (pinfunction "68_68") (pintype "passive"))
    )
    (net (code "229") (name "SA0") (class "Default")
      (node (ref "IC2") (pin "97") (pinfunction "97FB2MC8_97") (pintype "bidirectional"))
      (node (ref "IC3") (pin "22") (pinfunction "A0_22") (pintype "input"))
    )
    (net (code "230") (name "SA12") (class "Default")
      (node (ref "IC2") (pin "96") (pinfunction "96FB2MC6_96") (pintype "bidirectional"))
      (node (ref "IC3") (pin "35") (pinfunction "A12_35") (pintype "input"))
    )
    (net (code "231") (name "TCK") (class "Default")
      (node (ref "IC2") (pin "48") (pinfunction "48TCK_48") (pintype "bidirectional"))
      (node (ref "JP1") (pin "1") (pinfunction "1_1") (pintype "passive"))
      (node (ref "R22") (pin "1") (pinfunction "1_1") (pintype "passive"))
    )
    (net (code "232") (name "TDI") (class "Default")
      (node (ref "IC2") (pin "45") (pinfunction "45TDI_45") (pintype "bidirectional"))
      (node (ref "JP1") (pin "9") (pinfunction "9_9") (pintype "passive"))
      (node (ref "R24") (pin "1") (pinfunction "1_1") (pintype "passive"))
    )
    (net (code "233") (name "TDO") (class "Default")
      (node (ref "JP1") (pin "3") (pinfunction "3_3") (pintype "passive"))
      (node (ref "R25") (pin "2") (pinfunction "2_2") (pintype "passive"))
    )
    (net (code "234") (name "TMS") (class "Default")
      (node (ref "IC2") (pin "47") (pinfunction "47TMS_47") (pintype "bidirectional"))
      (node (ref "JP1") (pin "5") (pinfunction "5_5") (pintype "passive"))
      (node (ref "R23") (pin "1") (pinfunction "1_1") (pintype "passive"))
    )
    (net (code "235") (name "VA") (class "Default")
      (node (ref "IC11") (pin "6") (pinfunction "S2_6") (pintype "bidirectional"))
      (node (ref "JP2") (pin "11") (pinfunction "11_11") (pintype "passive"))
    )
    (net (code "236") (name "VB") (class "Default")
      (node (ref "C20") (pin "1") (pinfunction "1_1") (pintype "passive"))
      (node (ref "IC11") (pin "4") (pinfunction "S1_4") (pintype "bidirectional"))
      (node (ref "R36") (pin "2") (pinfunction "2_2") (pintype "passive"))
    )
    (net (code "237") (name "VCC") (class "Default")
      (node (ref "C13") (pin "1") (pinfunction "1_1") (pintype "passive"))
      (node (ref "C17") (pin "2") (pinfunction "2_2") (pintype "passive"))
      (node (ref "C18") (pin "2") (pinfunction "2_2") (pintype "passive"))
      (node (ref "C22") (pin "2") (pinfunction "2_2") (pintype "passive"))
      (node (ref "C24") (pin "2") (pinfunction "2_2") (pintype "passive"))
      (node (ref "C27") (pin "1") (pinfunction "1_1") (pintype "passive"))
      (node (ref "C28") (pin "2") (pinfunction "2_2") (pintype "passive"))
      (node (ref "C36") (pin "1") (pinfunction "1_1") (pintype "passive"))
      (node (ref "C37") (pin "1") (pinfunction "1_1") (pintype "passive"))
      (node (ref "D3") (pin "2") (pinfunction "K_2") (pintype "bidirectional"))
      (node (ref "FB1") (pin "1") (pinfunction "1_1") (pintype "passive"))
      (node (ref "FB2") (pin "2") (pinfunction "2_2") (pintype "passive"))
      (node (ref "FB3") (pin "2") (pinfunction "2_2") (pintype "passive"))
      (node (ref "FB4") (pin "2") (pinfunction "2_2") (pintype "passive"))
      (node (ref "IC1") (pin "3") (pinfunction "VIN_3") (pintype "input"))
      (node (ref "JP1") (pin "4") (pinfunction "4_4") (pintype "passive"))
      (node (ref "R22") (pin "2") (pinfunction "2_2") (pintype "passive"))
      (node (ref "R23") (pin "2") (pinfunction "2_2") (pintype "passive"))
      (node (ref "R24") (pin "2") (pinfunction "2_2") (pintype "passive"))
      (node (ref "R33") (pin "2") (pinfunction "P$2_2") (pintype "bidirectional"))
      (node (ref "R34") (pin "2") (pinfunction "P$2_2") (pintype "bidirectional"))
      (node (ref "R35") (pin "2") (pinfunction "2_2") (pintype "passive"))
      (node (ref "R44") (pin "2") (pinfunction "2_2") (pintype "passive"))
      (node (ref "R45") (pin "2") (pinfunction "2_2") (pintype "passive"))
      (node (ref "R7") (pin "2") (pinfunction "2_2") (pintype "passive"))
      (node (ref "ST1") (pin "5") (pinfunction "5_5") (pintype "passive"))
      (node (ref "ST1") (pin "6") (pinfunction "6_6") (pintype "passive"))
      (node (ref "X1") (pin "5") (pinfunction "5_5") (pintype "passive"))
      (node (ref "X1") (pin "6") (pinfunction "6_6") (pintype "passive"))
    )
    (net (code "238") (name "VO") (class "Default")
      (node (ref "FB8") (pin "1") (pinfunction "1_1") (pintype "passive"))
      (node (ref "IC11") (pin "5") (pinfunction "D_5") (pintype "bidirectional"))
    )
    (net (code "239") (name "VSYNC") (class "Default")
      (node (ref "IC3") (pin "96") (pinfunction "VSYNC_96") (pintype "output"))
      (node (ref "R36") (pin "1") (pinfunction "1_1") (pintype "passive"))
    )
    (net (code "240") (name "WAIT") (class "Default")
      (node (ref "IC2") (pin "93") (pinfunction "93FB2MC4_93") (pintype "bidirectional"))
      (node (ref "IC3") (pin "49") (pinfunction "IOCHRDY_49") (pintype "output"))
      (node (ref "R35") (pin "1") (pinfunction "1_1") (pintype "passive"))
    )
    (net (code "241") (name "XRDY") (class "Default")
      (node (ref "D2") (pin "1") (pinfunction "A_1") (pintype "bidirectional"))
      (node (ref "ST1") (pin "18") (pinfunction "18_18") (pintype "passive"))
      (node (ref "X1") (pin "18") (pinfunction "18_18") (pintype "passive"))
    )
    (net (code "242") (name "XRDYD") (class "Default")
      (node (ref "D2") (pin "2") (pinfunction "K_2") (pintype "bidirectional"))
      (node (ref "IC2") (pin "56") (pinfunction "56FB3MC15_56") (pintype "bidirectional"))
      (node (ref "R7") (pin "1") (pinfunction "1_1") (pintype "passive"))
    )
    (net (code "243") (name "unconnected-(IC2-2N.C.-Pad2)") (class "Default")
      (node (ref "IC2") (pin "2") (pinfunction "2N.C._2") (pintype "bidirectional"))
    )
    (net (code "244") (name "unconnected-(IC2-7N.C.-Pad7)") (class "Default")
      (node (ref "IC2") (pin "7") (pinfunction "7N.C._7") (pintype "bidirectional"))
    )
    (net (code "245") (name "unconnected-(IC2-19N.C.-Pad19)") (class "Default")
      (node (ref "IC2") (pin "19") (pinfunction "19N.C._19") (pintype "bidirectional"))
    )
    (net (code "246") (name "unconnected-(IC2-34N.C.-Pad34)") (class "Default")
      (node (ref "IC2") (pin "34") (pinfunction "34N.C._34") (pintype "bidirectional"))
    )
    (net (code "247") (name "unconnected-(IC2-43N.C.-Pad43)") (class "Default")
      (node (ref "IC2") (pin "43") (pinfunction "43N.C._43") (pintype "bidirectional"))
    )
    (net (code "248") (name "unconnected-(IC2-73N.C.-Pad73)") (class "Default")
      (node (ref "IC2") (pin "73") (pinfunction "73N.C._73") (pintype "bidirectional"))
    )
    (net (code "249") (name "unconnected-(IC2-80N.C.-Pad80)") (class "Default")
      (node (ref "IC2") (pin "80") (pinfunction "80N.C._80") (pintype "bidirectional"))
    )
    (net (code "250") (name "unconnected-(IC3-BLANK-Pad126)") (class "Default")
      (node (ref "IC3") (pin "126") (pinfunction "BLANK_126") (pintype "bidirectional"))
    )
    (net (code "251") (name "unconnected-(IC3-DCLK-Pad125)") (class "Default")
      (node (ref "IC3") (pin "125") (pinfunction "DCLK_125") (pintype "bidirectional"))
    )
    (net (code "252") (name "unconnected-(IC3-EDCLK-Pad123)") (class "Default")
      (node (ref "IC3") (pin "123") (pinfunction "EDCLK_123") (pintype "input"))
    )
    (net (code "253") (name "unconnected-(IC3-EECS-Pad107)") (class "Default")
      (node (ref "IC3") (pin "107") (pinfunction "EECS_107") (pintype "output"))
    )
    (net (code "254") (name "unconnected-(IC3-EEDI-Pad106)") (class "Default")
      (node (ref "IC3") (pin "106") (pinfunction "EEDI_106") (pintype "input"))
    )
    (net (code "255") (name "unconnected-(IC3-EROM-Pad33)") (class "Default")
      (node (ref "IC3") (pin "33") (pinfunction "EROM_33") (pintype "output"))
    )
    (net (code "256") (name "unconnected-(IC3-ESYNC-Pad122)") (class "Default")
      (node (ref "IC3") (pin "122") (pinfunction "ESYNC_122") (pintype "bidirectional"))
    )
    (net (code "257") (name "unconnected-(IC3-EVIDEO-Pad120)") (class "Default")
      (node (ref "IC3") (pin "120") (pinfunction "EVIDEO_120") (pintype "bidirectional"))
    )
    (net (code "258") (name "unconnected-(IC3-IOCS16-Pad72)") (class "Default")
      (node (ref "IC3") (pin "72") (pinfunction "IOCS16_72") (pintype "output"))
    )
    (net (code "259") (name "unconnected-(IC3-IRQ-Pad73)") (class "Default")
      (node (ref "IC3") (pin "73") (pinfunction "IRQ_73") (pintype "output"))
    )
    (net (code "260") (name "unconnected-(IC3-MA9-Pad190)") (class "Default")
      (node (ref "IC3") (pin "190") (pinfunction "MA9_190") (pintype "output"))
    )
    (net (code "261") (name "unconnected-(IC3-MCS16-Pad65)") (class "Default")
      (node (ref "IC3") (pin "65") (pinfunction "MCS16_65") (pintype "output"))
    )
    (net (code "262") (name "unconnected-(IC3-OVRW-Pad109)") (class "Default")
      (node (ref "IC3") (pin "109") (pinfunction "OVRW_109") (pintype "output"))
    )
    (net (code "263") (name "unconnected-(IC3-OWS-Pad19)") (class "Default")
      (node (ref "IC3") (pin "19") (pinfunction "OWS_19") (pintype "output"))
    )
    (net (code "264") (name "unconnected-(IC3-P0-Pad110)") (class "Default")
      (node (ref "IC3") (pin "110") (pinfunction "P0_110") (pintype "bidirectional"))
    )
    (net (code "265") (name "unconnected-(IC3-P1-Pad111)") (class "Default")
      (node (ref "IC3") (pin "111") (pinfunction "P1_111") (pintype "bidirectional"))
    )
    (net (code "266") (name "unconnected-(IC3-P2-Pad112)") (class "Default")
      (node (ref "IC3") (pin "112") (pinfunction "P2_112") (pintype "bidirectional"))
    )
    (net (code "267") (name "unconnected-(IC3-P3-Pad113)") (class "Default")
      (node (ref "IC3") (pin "113") (pinfunction "P3_113") (pintype "bidirectional"))
    )
    (net (code "268") (name "unconnected-(IC3-P4-Pad115)") (class "Default")
      (node (ref "IC3") (pin "115") (pinfunction "P4_115") (pintype "bidirectional"))
    )
    (net (code "269") (name "unconnected-(IC3-P5-Pad116)") (class "Default")
      (node (ref "IC3") (pin "116") (pinfunction "P5_116") (pintype "bidirectional"))
    )
    (net (code "270") (name "unconnected-(IC3-P6-Pad117)") (class "Default")
      (node (ref "IC3") (pin "117") (pinfunction "P6_117") (pintype "bidirectional"))
    )
    (net (code "271") (name "unconnected-(IC3-P7-Pad118)") (class "Default")
      (node (ref "IC3") (pin "118") (pinfunction "P7_118") (pintype "bidirectional"))
    )
    (net (code "272") (name "unconnected-(IC3-RAS0-Pad169)") (class "Default")
      (node (ref "IC3") (pin "169") (pinfunction "RAS0_169") (pintype "output"))
    )
    (net (code "273") (name "unconnected-(IC210-4A-Pad10)") (class "Default")
      (node (ref "IC210") (pin "10") (pinfunction "4A_10") (pintype "bidirectional"))
    )
    (net (code "274") (name "unconnected-(JP1-Pad6)") (class "Default")
      (node (ref "JP1") (pin "6") (pinfunction "6_6") (pintype "passive"))
    )
    (net (code "275") (name "unconnected-(JP1-Pad7)") (class "Default")
      (node (ref "JP1") (pin "7") (pinfunction "7_7") (pintype "passive"))
    )
    (net (code "276") (name "unconnected-(JP1-Pad8)") (class "Default")
      (node (ref "JP1") (pin "8") (pinfunction "8_8") (pintype "passive"))
    )
    (net (code "277") (name "unconnected-(R4D-P$2-PadP$5)") (class "Default")
      (node (ref "R4") (pin "P$5") (pinfunction "P$2_P$5") (pintype "bidirectional"))
    )
    (net (code "278") (name "unconnected-(ST1-Pad20)") (class "Default")
      (node (ref "ST1") (pin "20") (pinfunction "20_20") (pintype "passive"))
    )
    (net (code "279") (name "unconnected-(ST1-Pad40)") (class "Default")
      (node (ref "ST1") (pin "40") (pinfunction "40_40") (pintype "passive"))
    )
    (net (code "280") (name "unconnected-(ST1-Pad42)") (class "Default")
      (node (ref "ST1") (pin "42") (pinfunction "42_42") (pintype "passive"))
    )
    (net (code "281") (name "unconnected-(ST1-Pad44)") (class "Default")
      (node (ref "ST1") (pin "44") (pinfunction "44_44") (pintype "passive"))
    )
    (net (code "282") (name "unconnected-(X1-Pad7)") (class "Default")
      (node (ref "X1") (pin "7") (pinfunction "7_7") (pintype "passive"))
    )
    (net (code "283") (name "unconnected-(X1-Pad20)") (class "Default")
      (node (ref "X1") (pin "20") (pinfunction "20_20") (pintype "passive"))
    )
    (net (code "284") (name "unconnected-(X1-Pad40)") (class "Default")
      (node (ref "X1") (pin "40") (pinfunction "40_40") (pintype "passive"))
    )
    (net (code "285") (name "unconnected-(X1-Pad42)") (class "Default")
      (node (ref "X1") (pin "42") (pinfunction "42_42") (pintype "passive"))
    )
    (net (code "286") (name "unconnected-(X1-Pad44)") (class "Default")
      (node (ref "X1") (pin "44") (pinfunction "44_44") (pintype "passive"))
    )
    (net (code "287") (name "{slash}AS") (class "Default")
      (node (ref "IC2") (pin "23") (pinfunction "23FB1MC10-I/O/GCK2_23") (pintype "bidirectional"))
      (node (ref "ST1") (pin "74") (pinfunction "74_74") (pintype "passive"))
      (node (ref "X1") (pin "74") (pinfunction "74_74") (pintype "passive"))
    )
    (net (code "288") (name "{slash}BERR") (class "Default")
      (node (ref "IC2") (pin "39") (pinfunction "39FB1MC16_39") (pintype "bidirectional"))
      (node (ref "ST1") (pin "46") (pinfunction "46_46") (pintype "passive"))
      (node (ref "X1") (pin "46") (pinfunction "46_46") (pintype "passive"))
    )
    (net (code "289") (name "{slash}BG") (class "Default")
      (node (ref "ST1") (pin "64") (pinfunction "64_64") (pintype "passive"))
      (node (ref "X1") (pin "64") (pinfunction "64_64") (pintype "passive"))
    )
    (net (code "290") (name "{slash}BGACK") (class "Default")
      (node (ref "ST1") (pin "62") (pinfunction "62_62") (pintype "passive"))
      (node (ref "X1") (pin "62") (pinfunction "62_62") (pintype "passive"))
    )
    (net (code "291") (name "{slash}BR") (class "Default")
      (node (ref "ST1") (pin "60") (pinfunction "60_60") (pintype "passive"))
      (node (ref "X1") (pin "60") (pinfunction "60_60") (pintype "passive"))
    )
    (net (code "292") (name "{slash}CCK") (class "Default")
      (node (ref "ST1") (pin "16") (pinfunction "16_16") (pintype "passive"))
      (node (ref "X1") (pin "16") (pinfunction "16_16") (pintype "passive"))
    )
    (net (code "293") (name "{slash}CCKQ") (class "Default")
      (node (ref "ST1") (pin "14") (pinfunction "14_14") (pintype "passive"))
      (node (ref "X1") (pin "14") (pinfunction "14_14") (pintype "passive"))
    )
    (net (code "294") (name "{slash}DS1") (class "Default")
      (node (ref "ST1") (pin "98") (pinfunction "98_98") (pintype "passive"))
    )
    (net (code "295") (name "{slash}DTACK") (class "Default")
      (node (ref "IC2") (pin "27") (pinfunction "27FB1MC14-I/O/GCK3_27") (pintype "bidirectional"))
      (node (ref "R44") (pin "1") (pinfunction "1_1") (pintype "passive"))
      (node (ref "ST1") (pin "66") (pinfunction "66_66") (pintype "passive"))
      (node (ref "X1") (pin "66") (pinfunction "66_66") (pintype "passive"))
    )
    (net (code "296") (name "{slash}EINT1") (class "Default")
      (node (ref "ST1") (pin "96") (pinfunction "96_96") (pintype "passive"))
    )
    (net (code "297") (name "{slash}FCS") (class "Default")
      (node (ref "ST1") (pin "97") (pinfunction "97_97") (pintype "passive"))
    )
    (net (code "298") (name "{slash}GBG") (class "Default")
      (node (ref "ST1") (pin "95") (pinfunction "95_95") (pintype "passive"))
    )
    (net (code "299") (name "{slash}HALT") (class "Default")
      (node (ref "ST1") (pin "55") (pinfunction "55_55") (pintype "passive"))
      (node (ref "X1") (pin "55") (pinfunction "55_55") (pintype "passive"))
    )
    (net (code "300") (name "{slash}INT2") (class "Default")
      (node (ref "ST1") (pin "19") (pinfunction "19_19") (pintype "passive"))
      (node (ref "X1") (pin "19") (pinfunction "19_19") (pintype "passive"))
    )
    (net (code "301") (name "{slash}INT6") (class "Default")
      (node (ref "ST1") (pin "22") (pinfunction "22_22") (pintype "passive"))
      (node (ref "X1") (pin "22") (pinfunction "22_22") (pintype "passive"))
    )
    (net (code "302") (name "{slash}LDS") (class "Default")
      (node (ref "IC2") (pin "18") (pinfunction "18FB1MC3_18") (pintype "bidirectional"))
      (node (ref "IC3") (pin "21") (pinfunction "SBHE_21") (pintype "input"))
      (node (ref "ST1") (pin "70") (pinfunction "70_70") (pintype "passive"))
      (node (ref "X1") (pin "70") (pinfunction "70_70") (pintype "passive"))
    )
    (net (code "303") (name "{slash}OVR") (class "Default")
      (node (ref "IC2") (pin "49") (pinfunction "49FB3MC3_49") (pintype "bidirectional"))
      (node (ref "R45") (pin "1") (pinfunction "1_1") (pintype "passive"))
      (node (ref "ST1") (pin "17") (pinfunction "17_17") (pintype "passive"))
      (node (ref "X1") (pin "17") (pinfunction "17_17") (pintype "passive"))
    )
    (net (code "304") (name "{slash}OWN") (class "Default")
      (node (ref "ST1") (pin "7") (pinfunction "7_7") (pintype "passive"))
    )
    (net (code "305") (name "{slash}RESETF") (class "Default")
      (node (ref "C11") (pin "2") (pinfunction "2_2") (pintype "passive"))
      (node (ref "IC2") (pin "99") (pinfunction "99FB2MC9-I/O/GSR_99") (pintype "bidirectional"))
      (node (ref "R8") (pin "2") (pinfunction "2_2") (pintype "passive"))
    )
    (net (code "306") (name "{slash}SERESET") (class "Default")
      (node (ref "R8") (pin "1") (pinfunction "1_1") (pintype "passive"))
      (node (ref "ST1") (pin "53") (pinfunction "53_53") (pintype "passive"))
      (node (ref "X1") (pin "53") (pinfunction "53_53") (pintype "passive"))
    )
    (net (code "307") (name "{slash}SLAVE") (class "Default")
      (node (ref "IC2") (pin "60") (pinfunction "60FB3MC10_60") (pintype "bidirectional"))
      (node (ref "ST1") (pin "9") (pinfunction "9_9") (pintype "passive"))
      (node (ref "X1") (pin "9") (pinfunction "9_9") (pintype "passive"))
    )
    (net (code "308") (name "{slash}UDS") (class "Default")
      (node (ref "IC2") (pin "16") (pinfunction "16FB1MC1_16") (pintype "bidirectional"))
      (node (ref "ST1") (pin "72") (pinfunction "72_72") (pintype "passive"))
      (node (ref "X1") (pin "72") (pinfunction "72_72") (pintype "passive"))
    )
    (net (code "309") (name "{slash}VMA") (class "Default")
      (node (ref "ST1") (pin "51") (pinfunction "51_51") (pintype "passive"))
      (node (ref "X1") (pin "51") (pinfunction "51_51") (pintype "passive"))
    )
    (net (code "310") (name "{slash}VPA") (class "Default")
      (node (ref "ST1") (pin "48") (pinfunction "48_48") (pintype "passive"))
      (node (ref "X1") (pin "48") (pinfunction "48_48") (pintype "passive"))
    )
  )
)
